# qsd67lc_v2.net
KiCad netlist of a schematic drawn in EAGLE
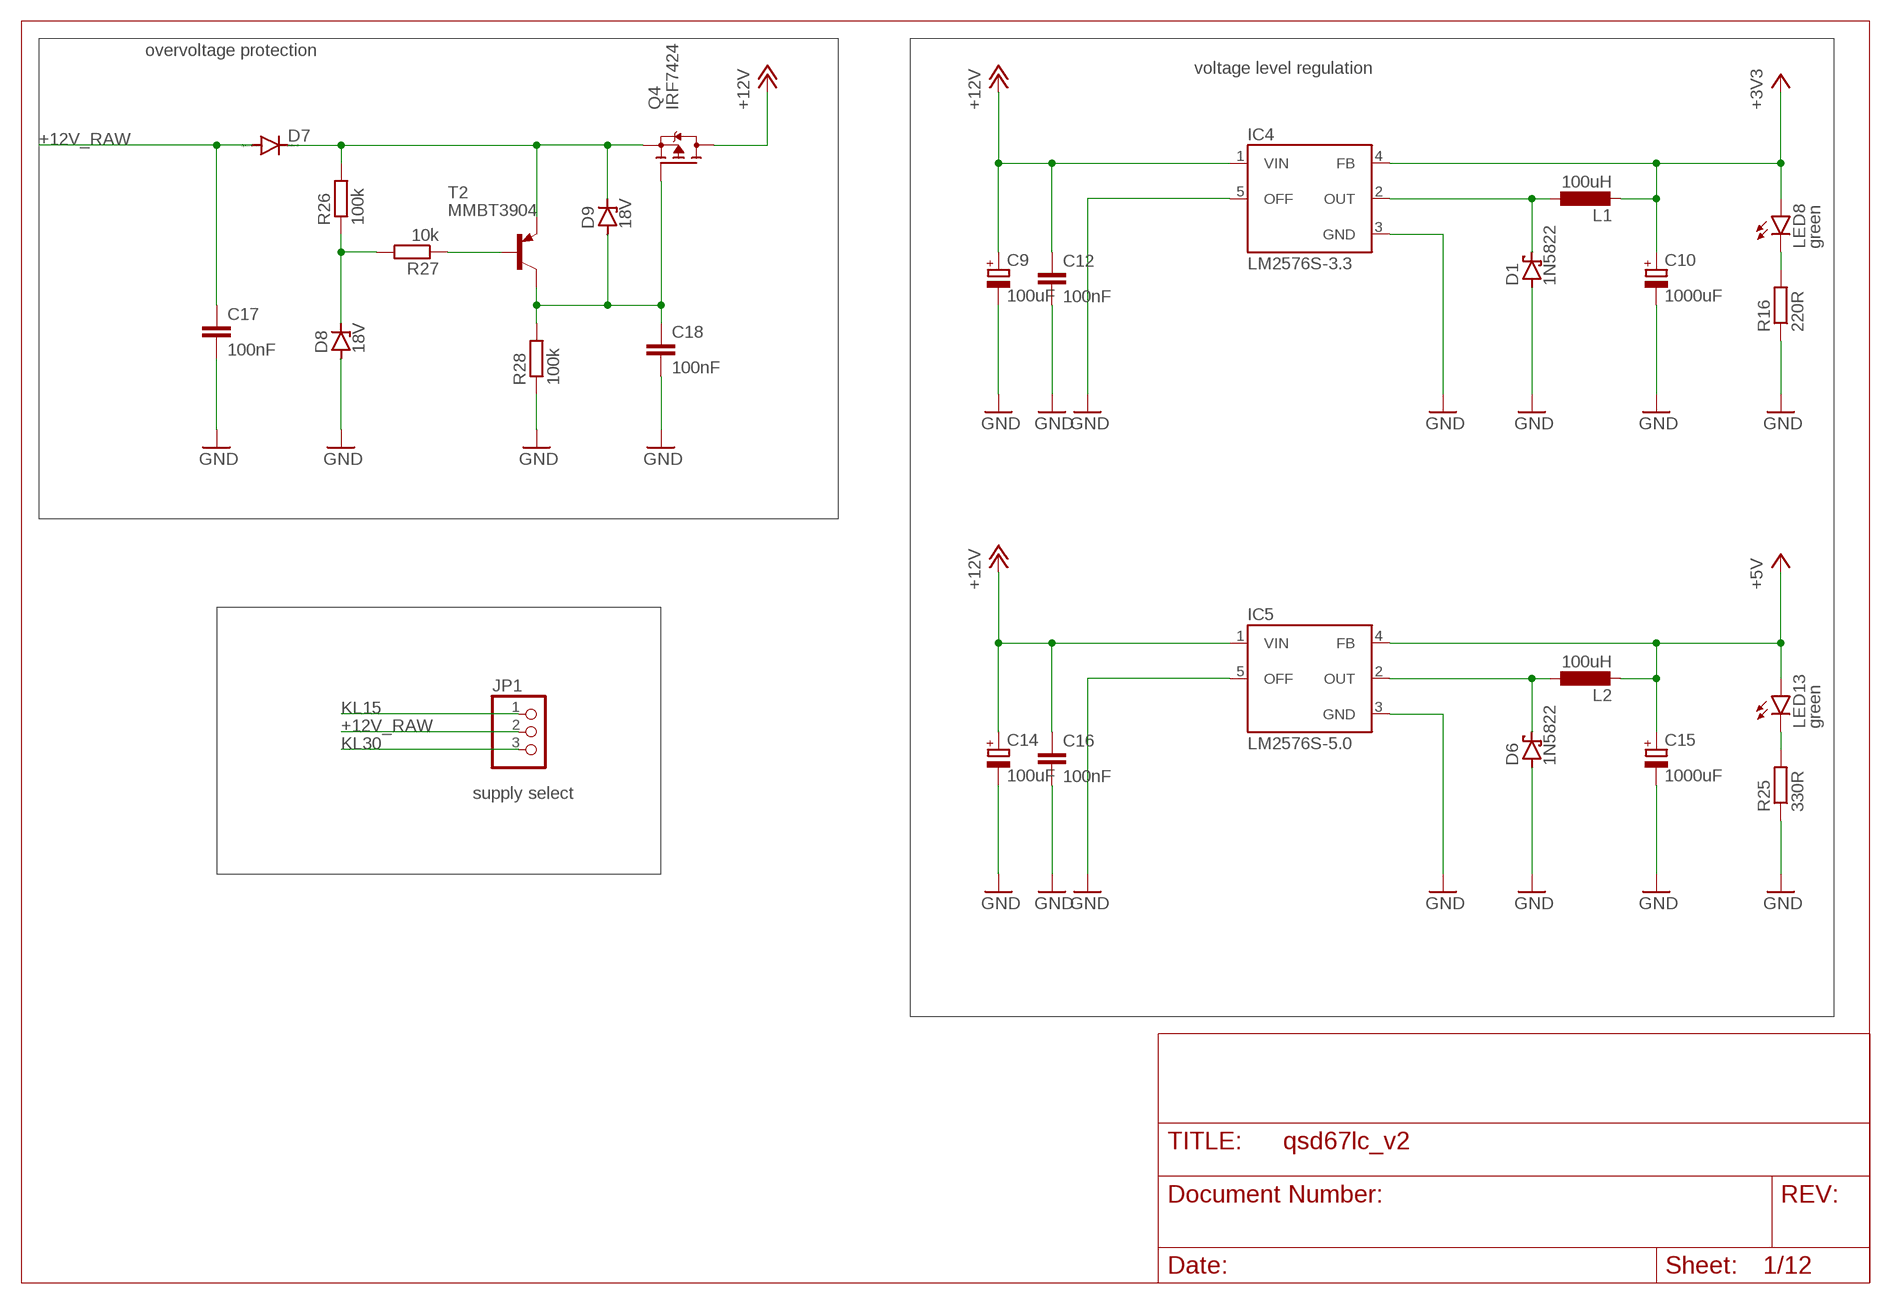
[diagram p0: schematic, sheet 1]
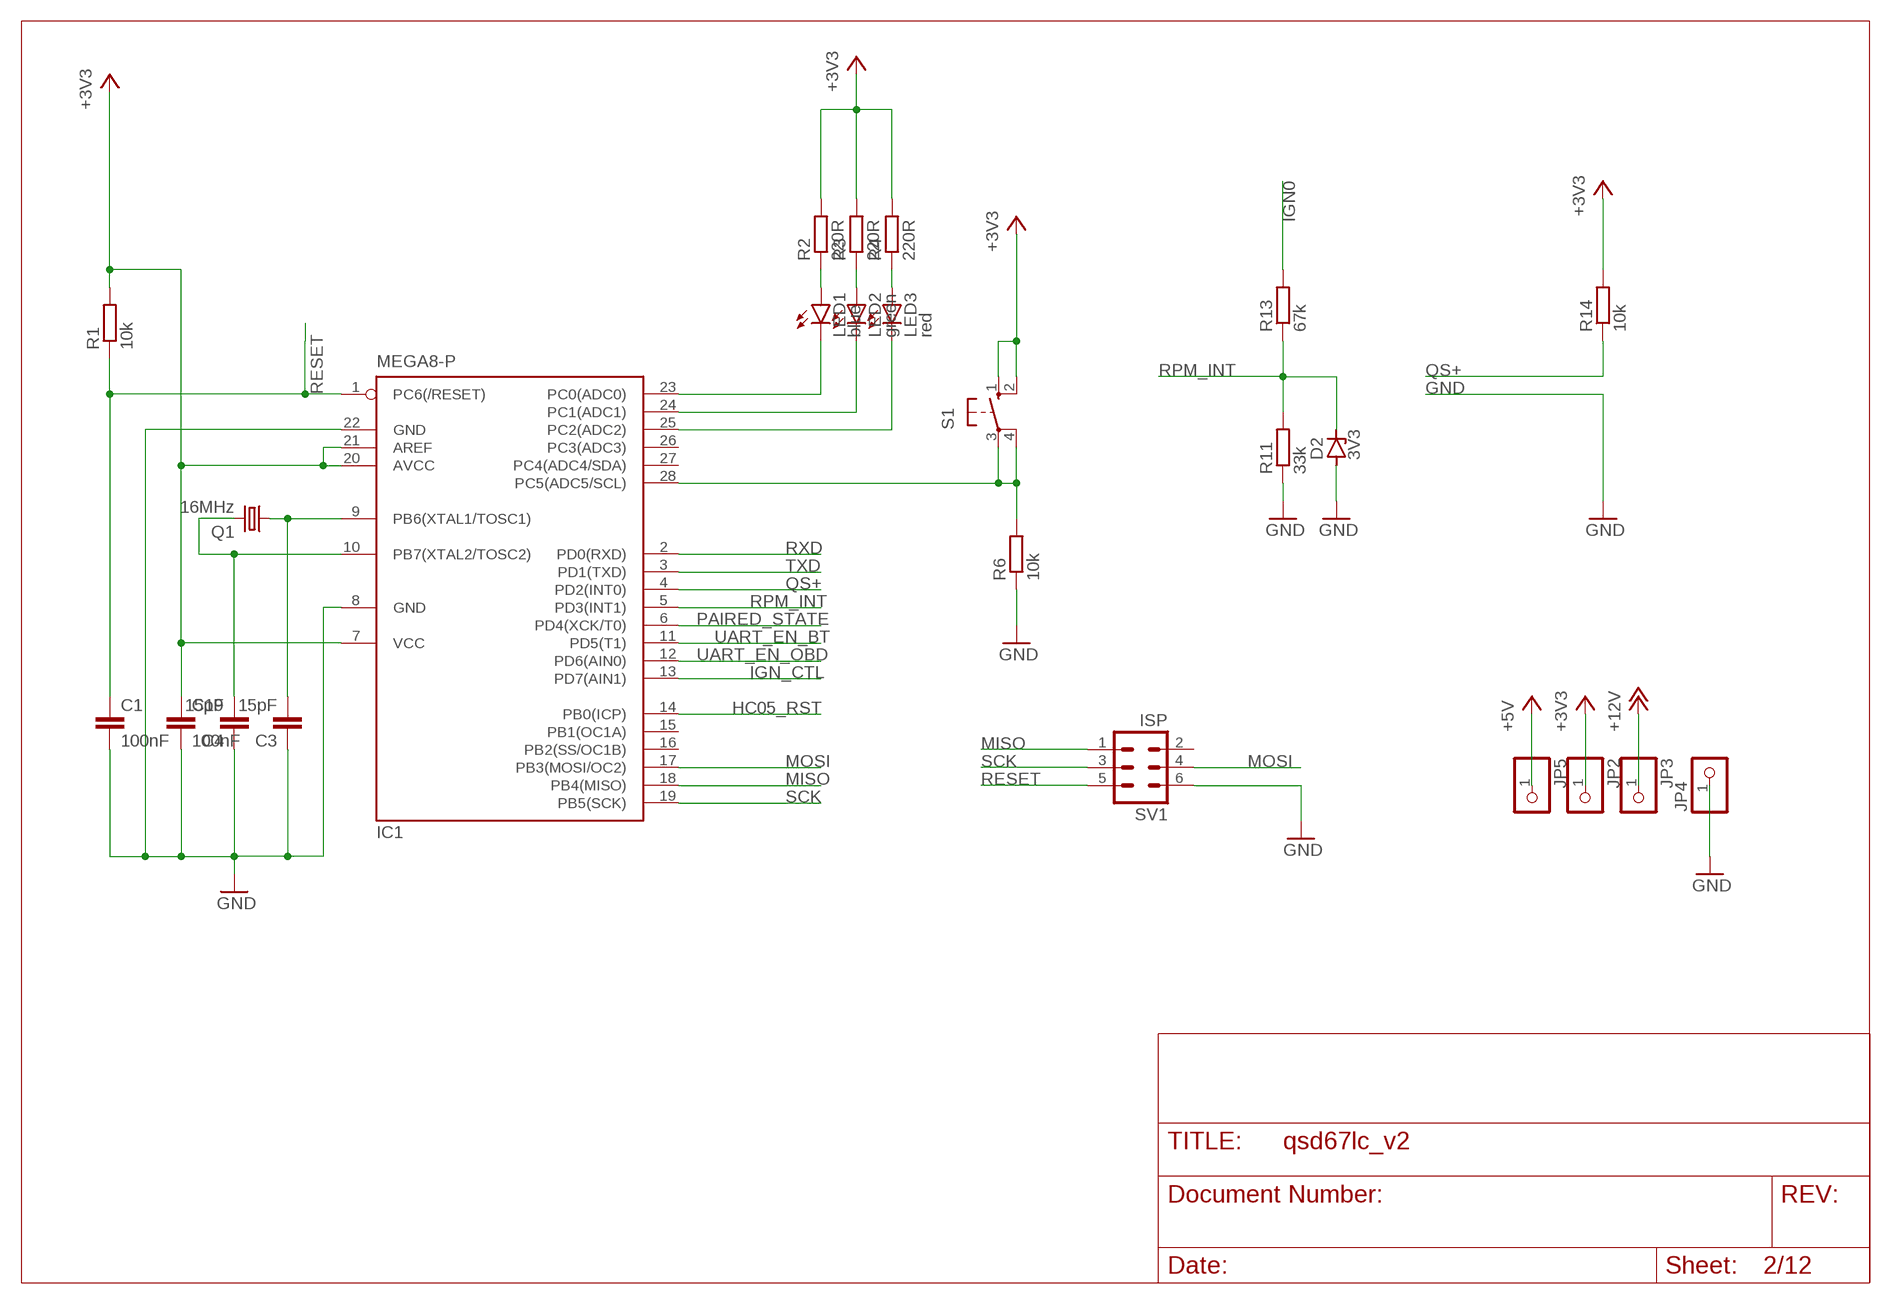
[diagram p1: schematic, sheet 2]
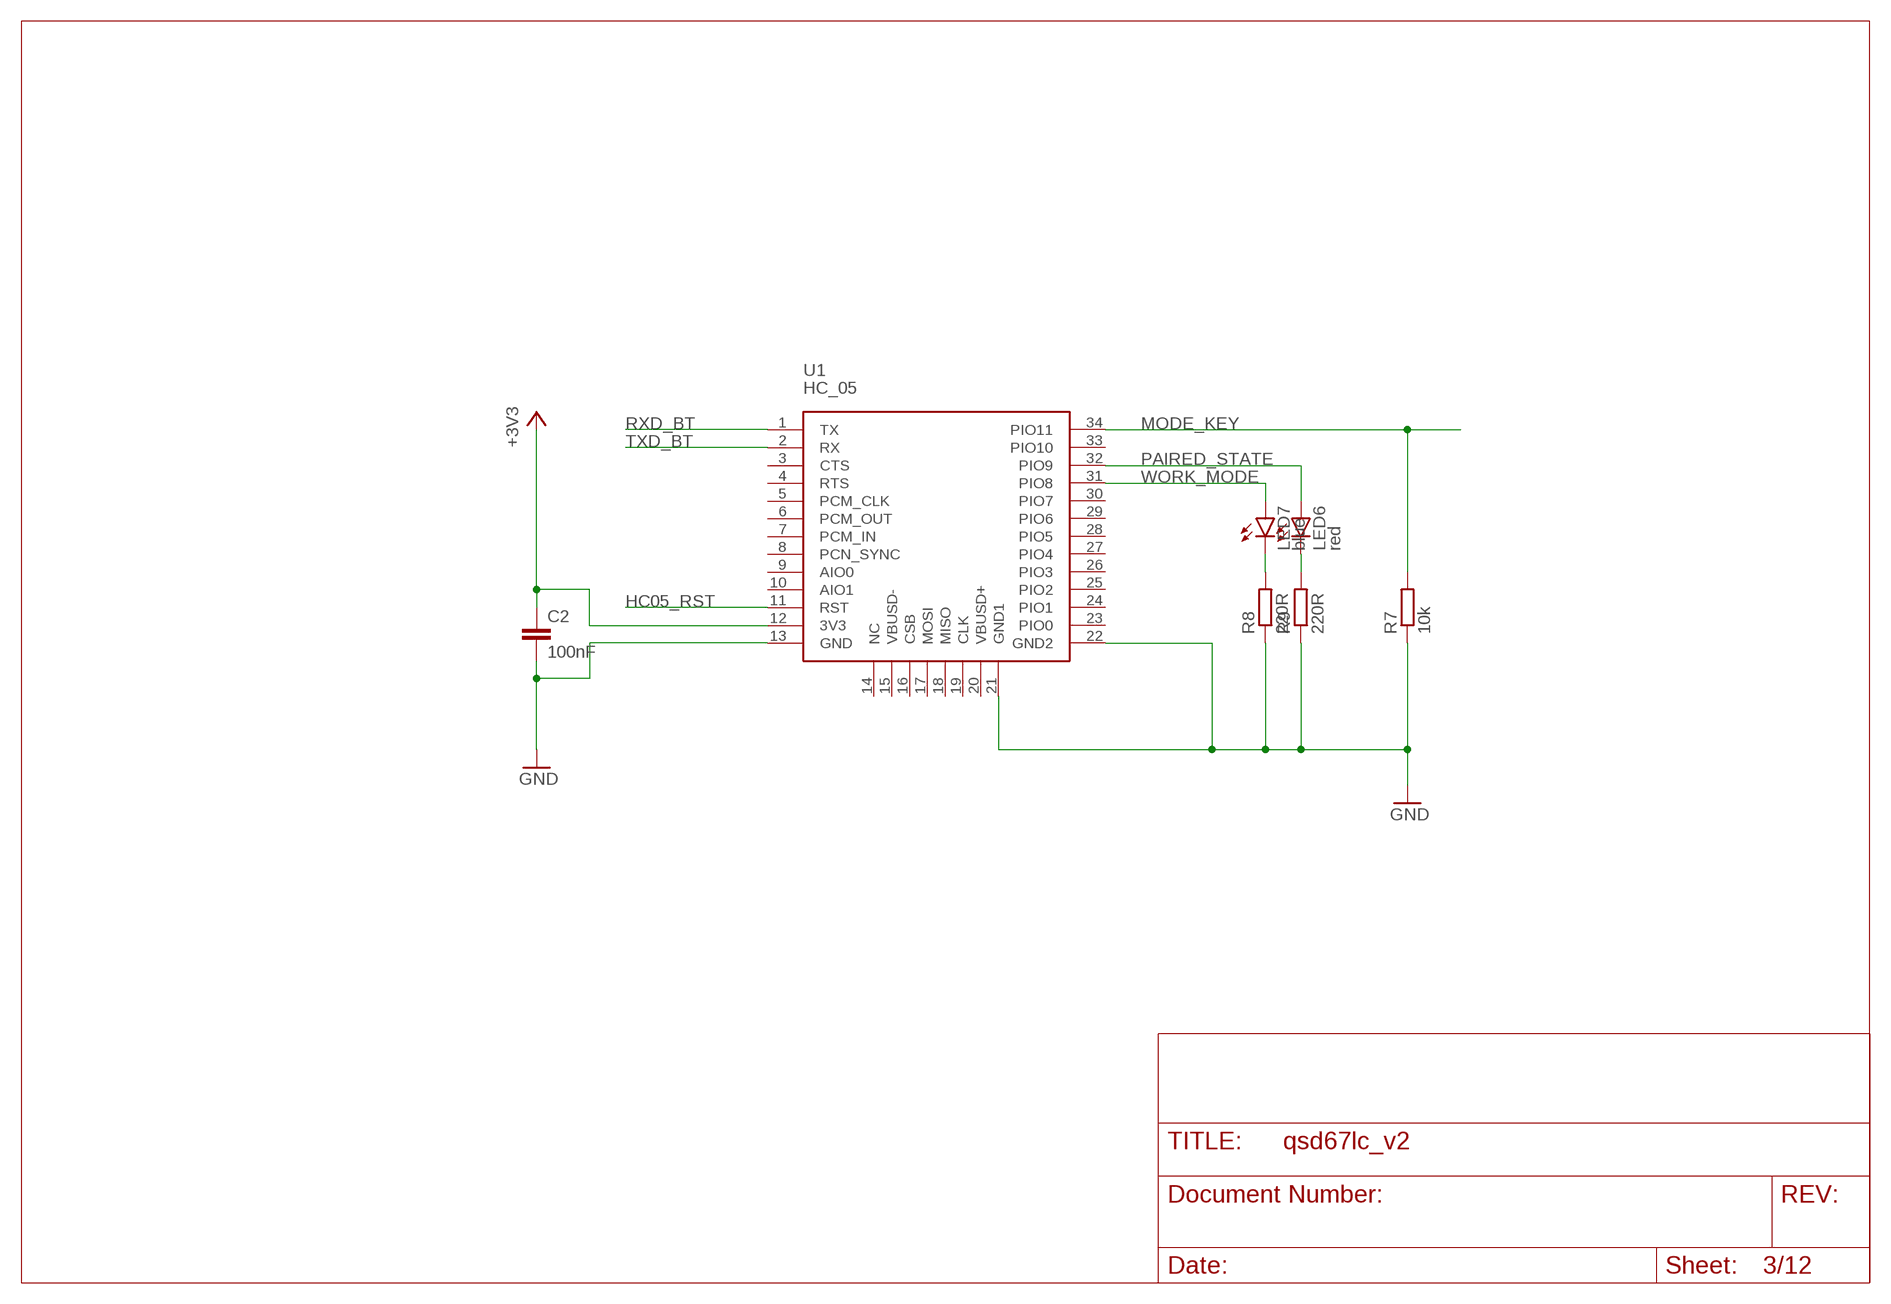
[diagram p2: schematic, sheet 3]
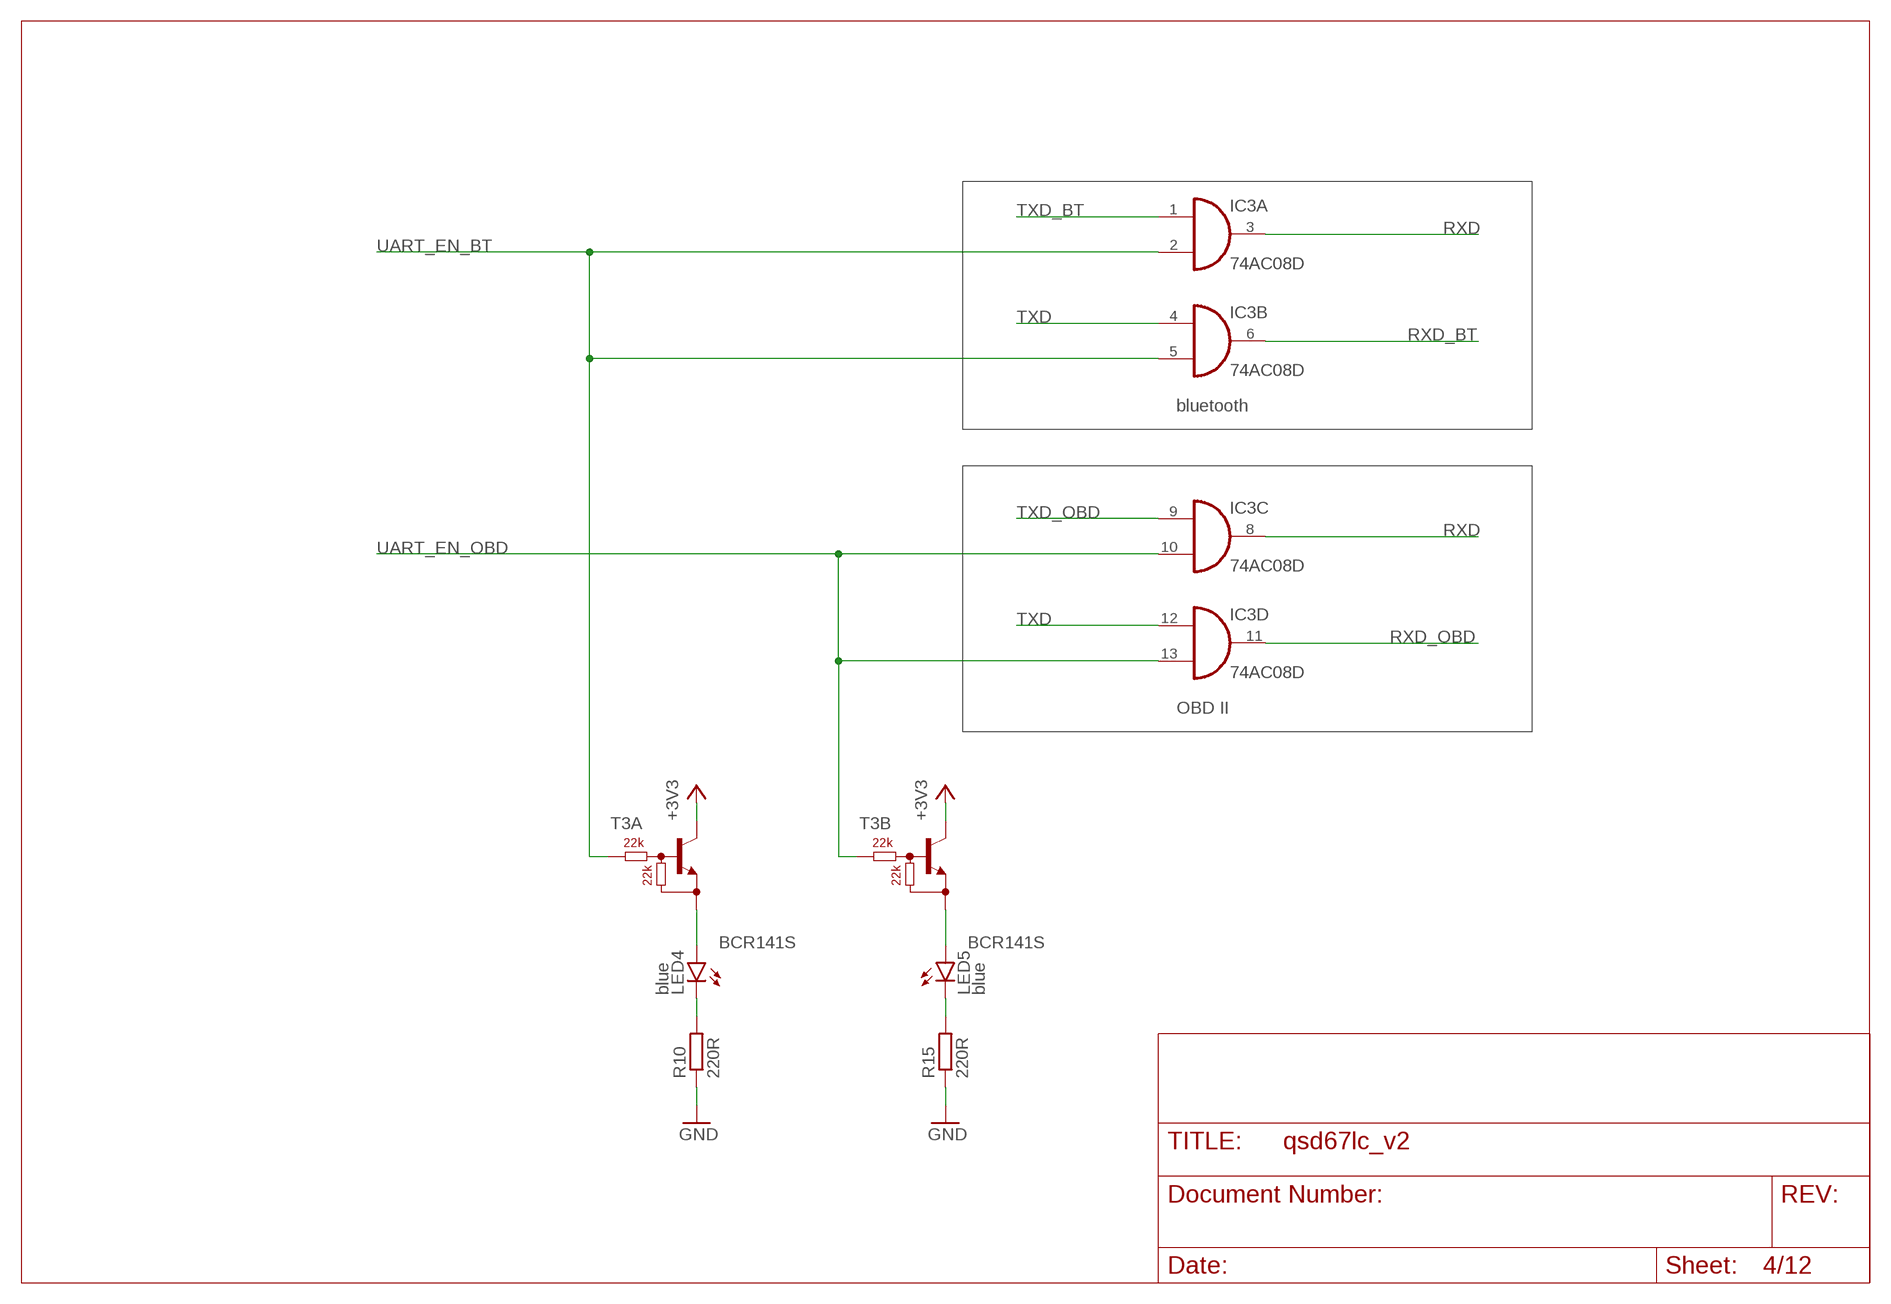
[diagram p3: schematic, sheet 4]
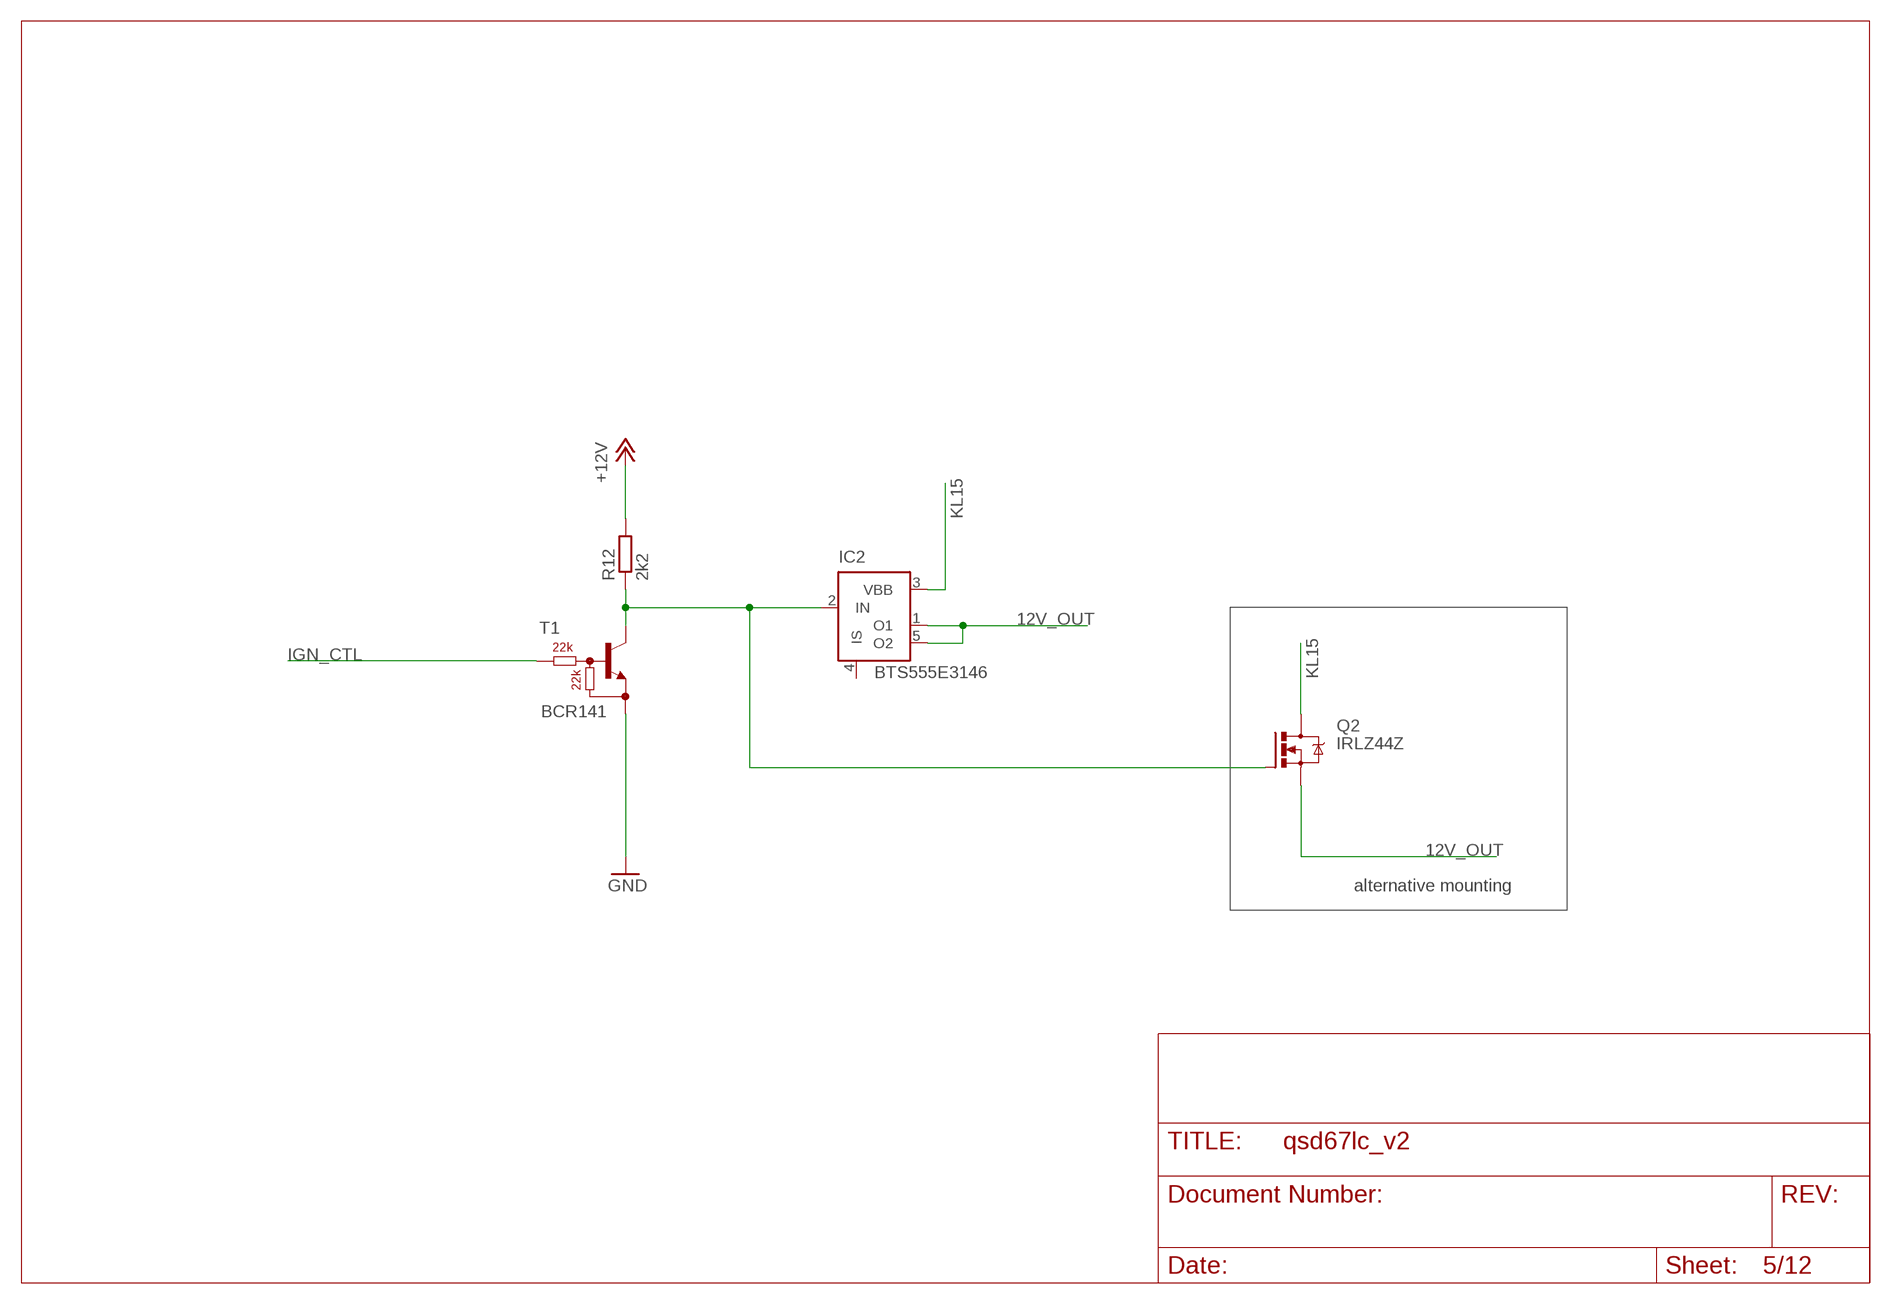
[diagram p4: schematic, sheet 5]
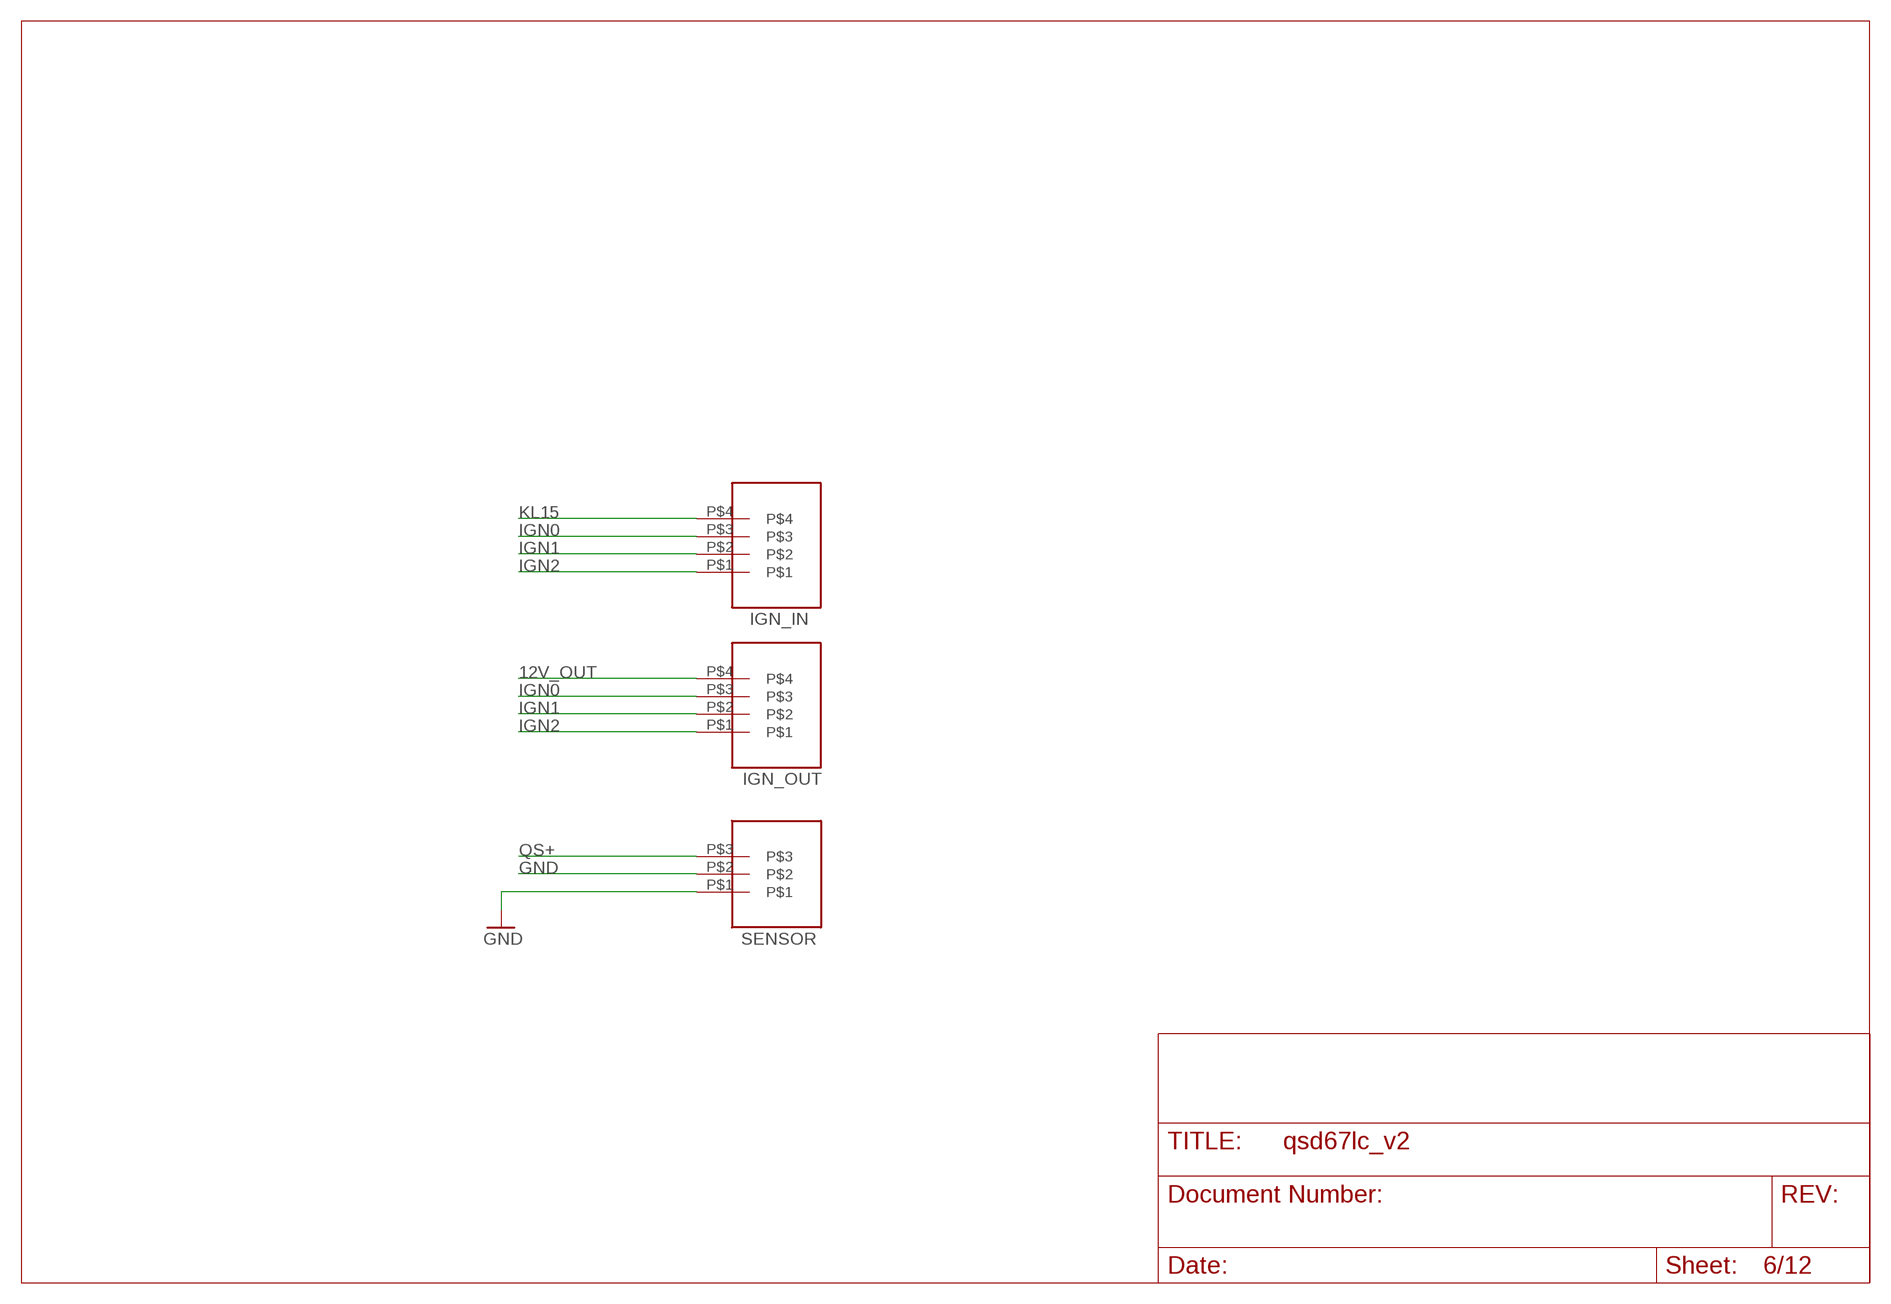
[diagram p5: schematic, sheet 6]
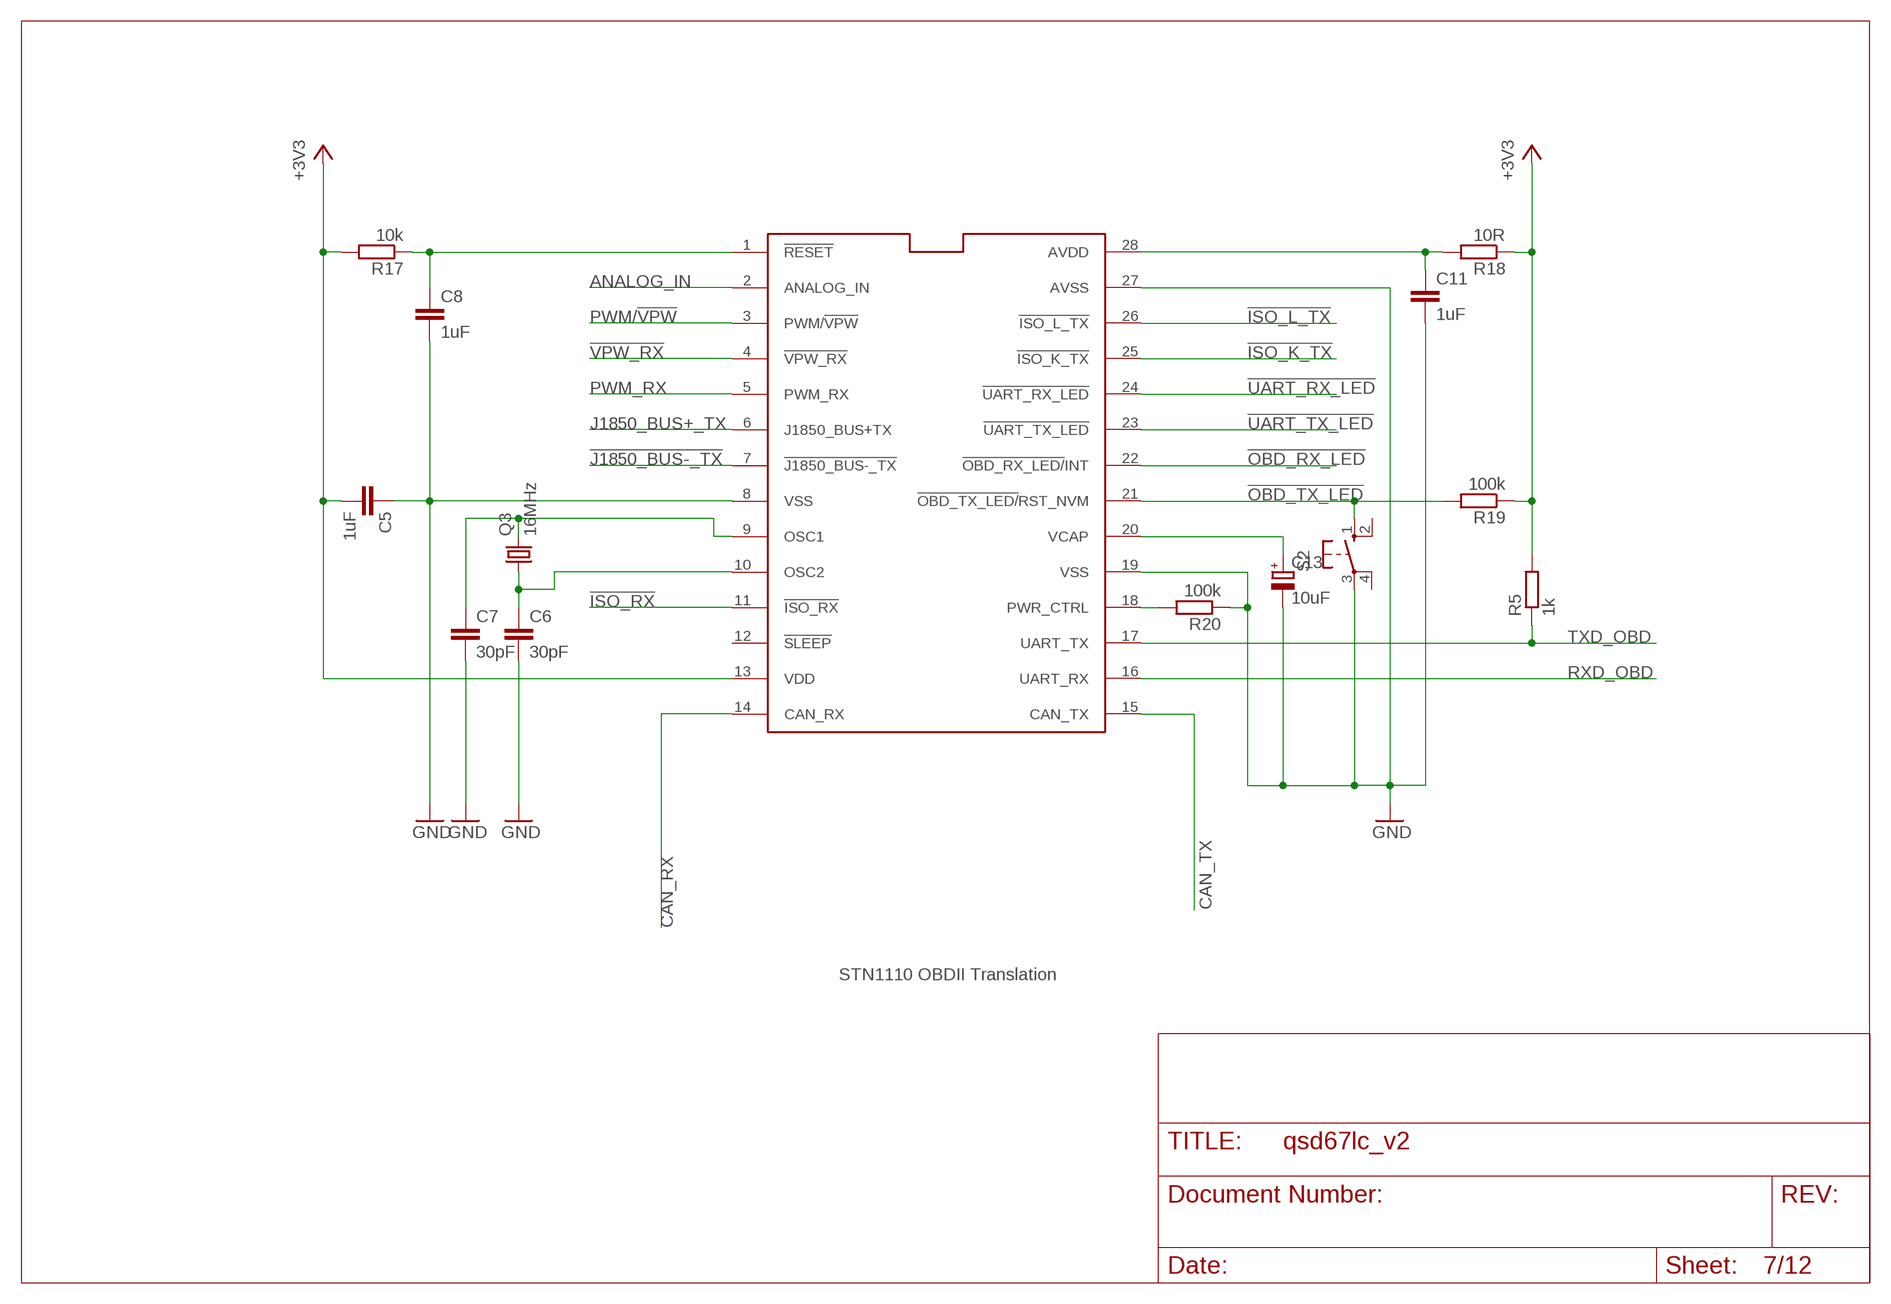
[diagram p6: schematic, sheet 7]
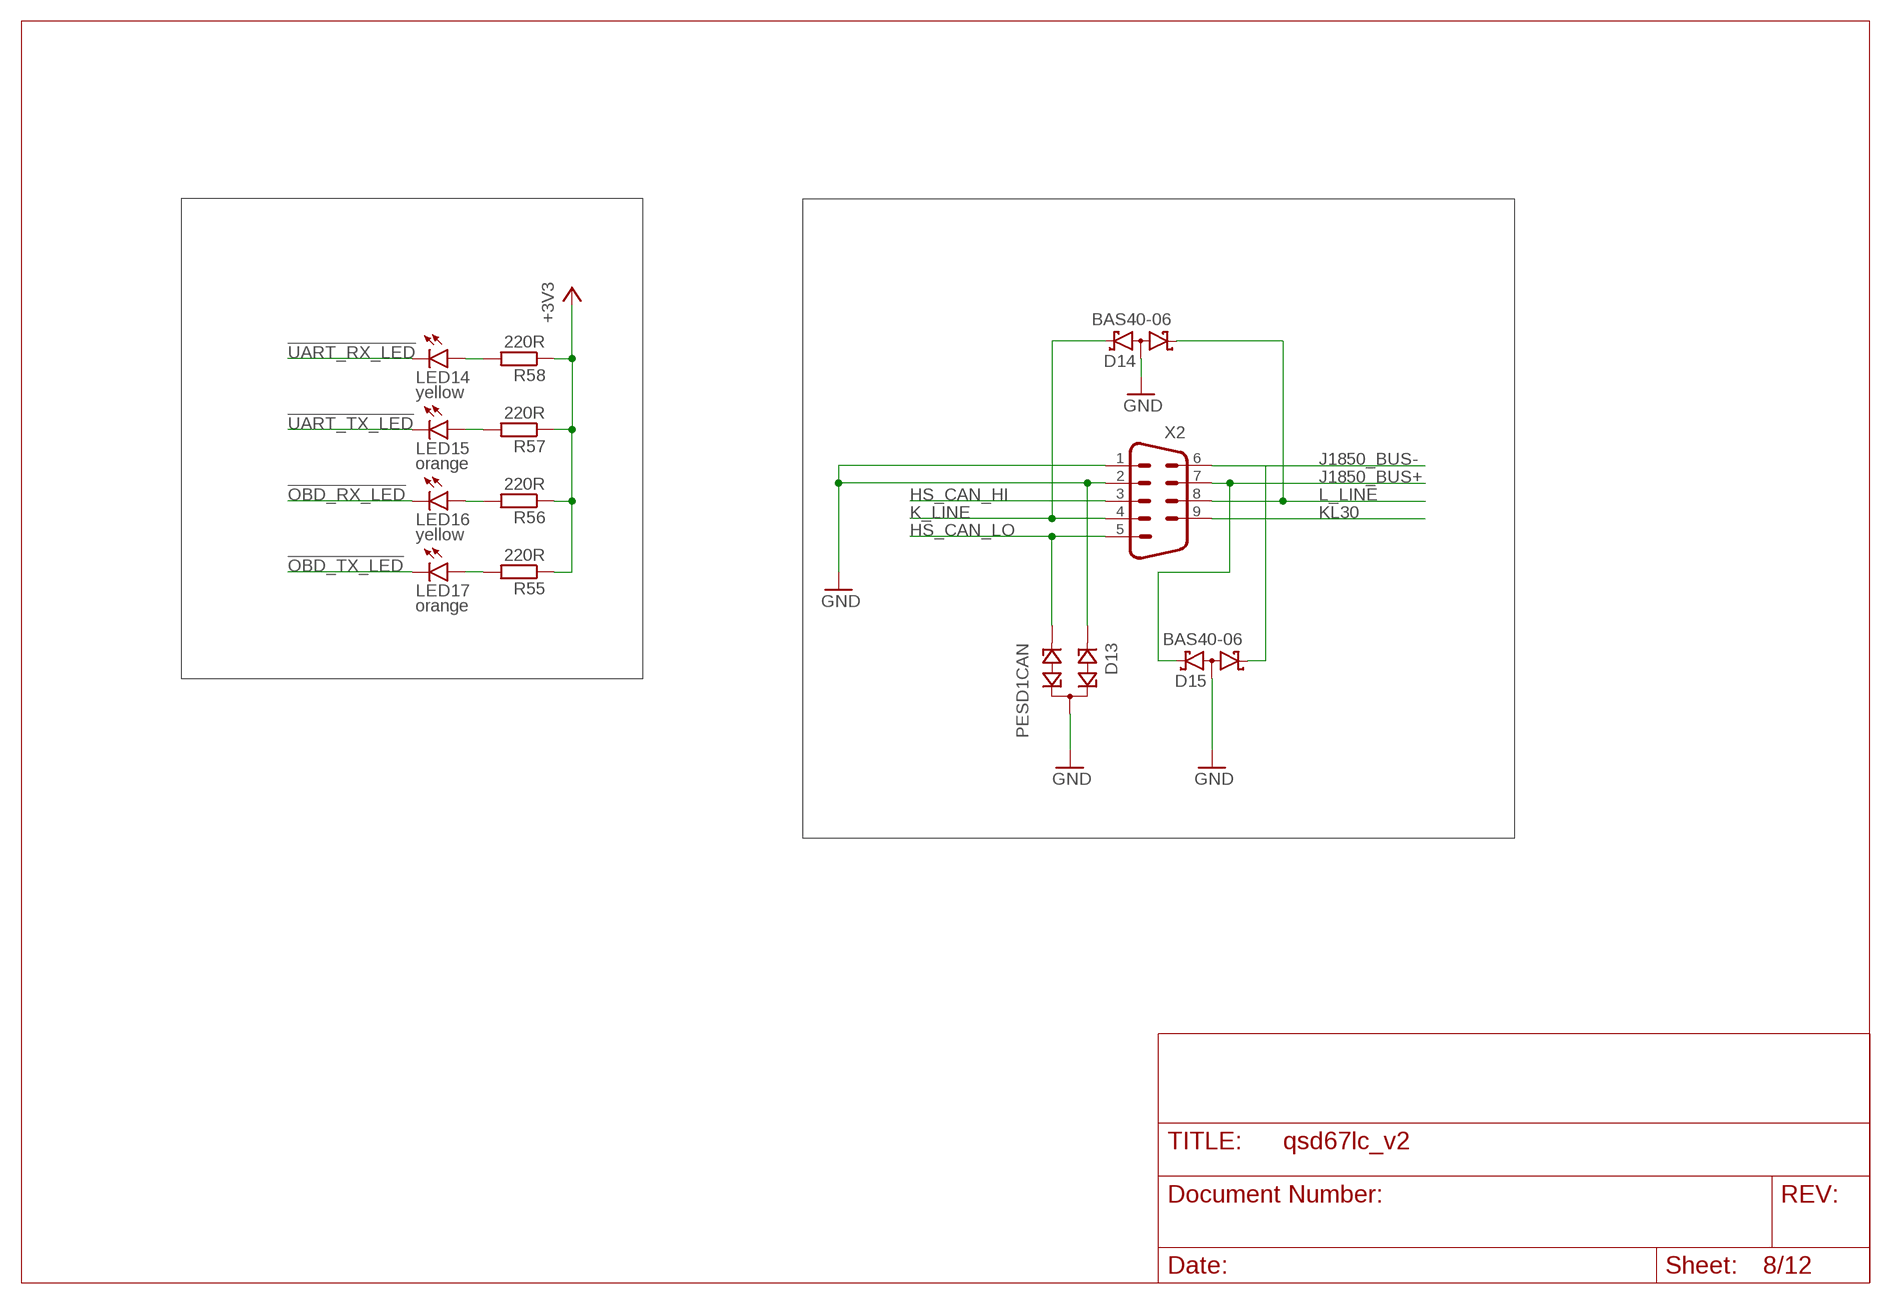
[diagram p7: schematic, sheet 8]
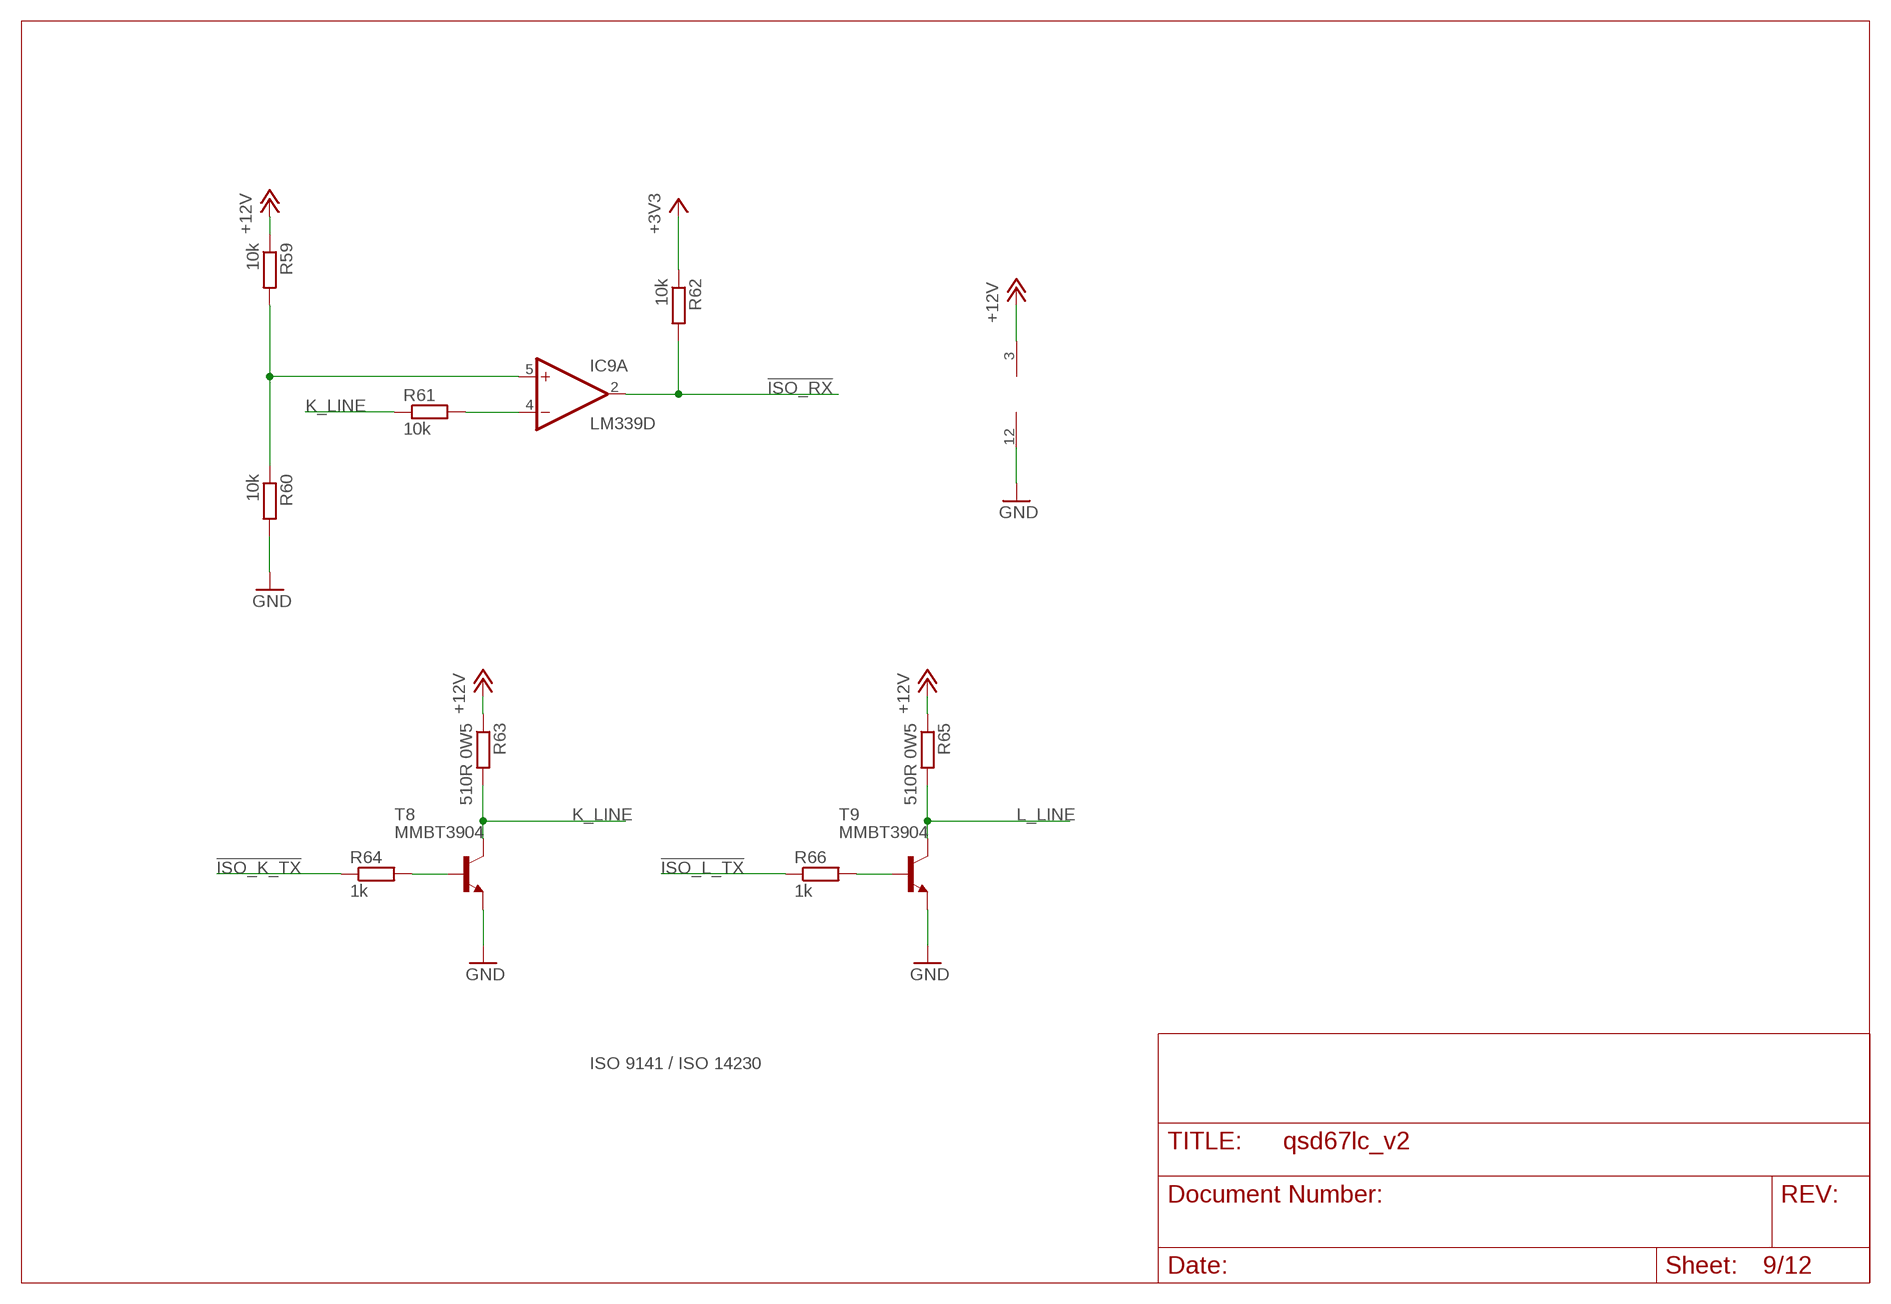
[diagram p8: schematic, sheet 9]
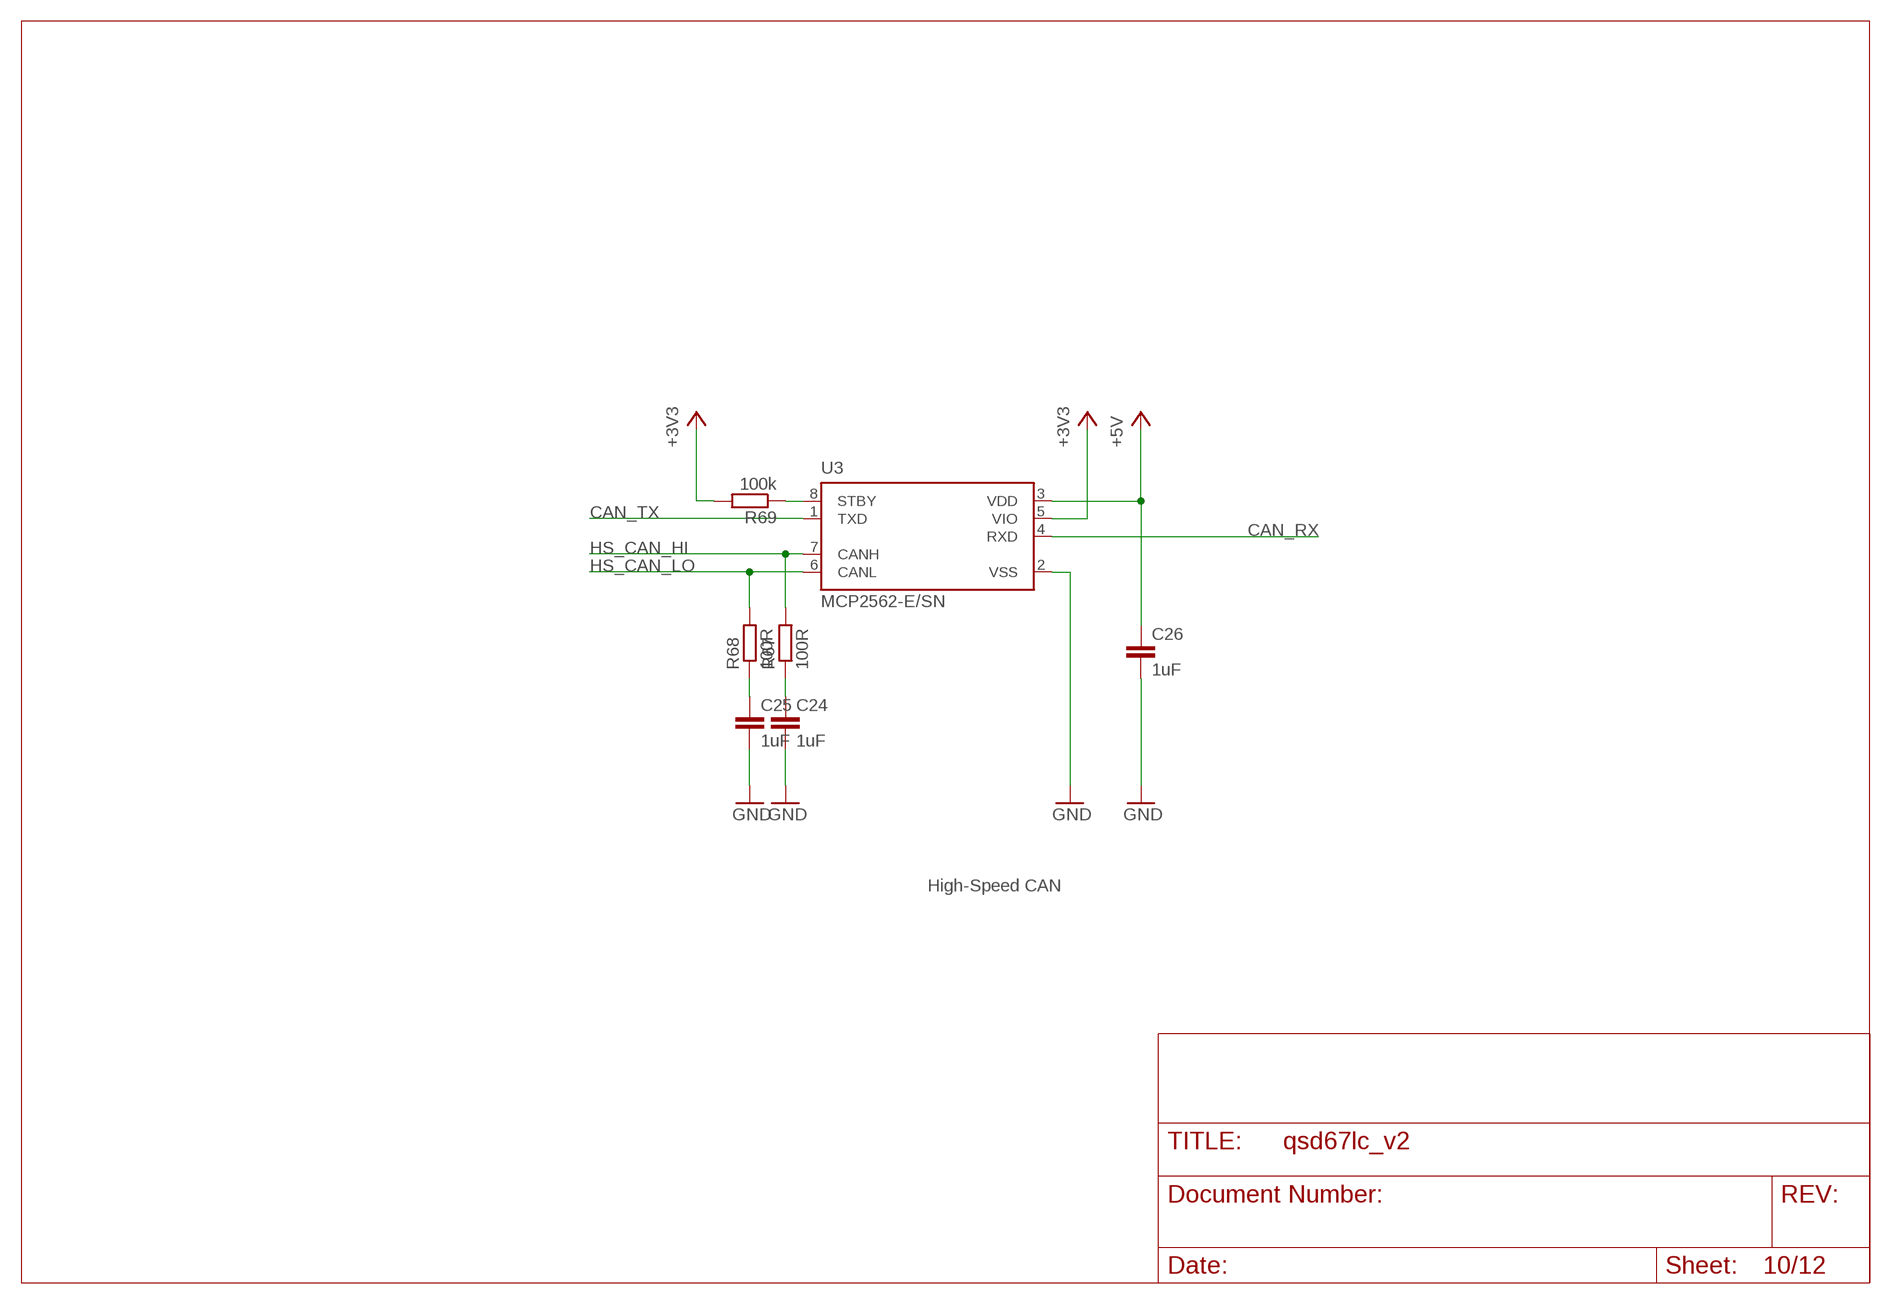
[diagram p9: schematic, sheet 10]
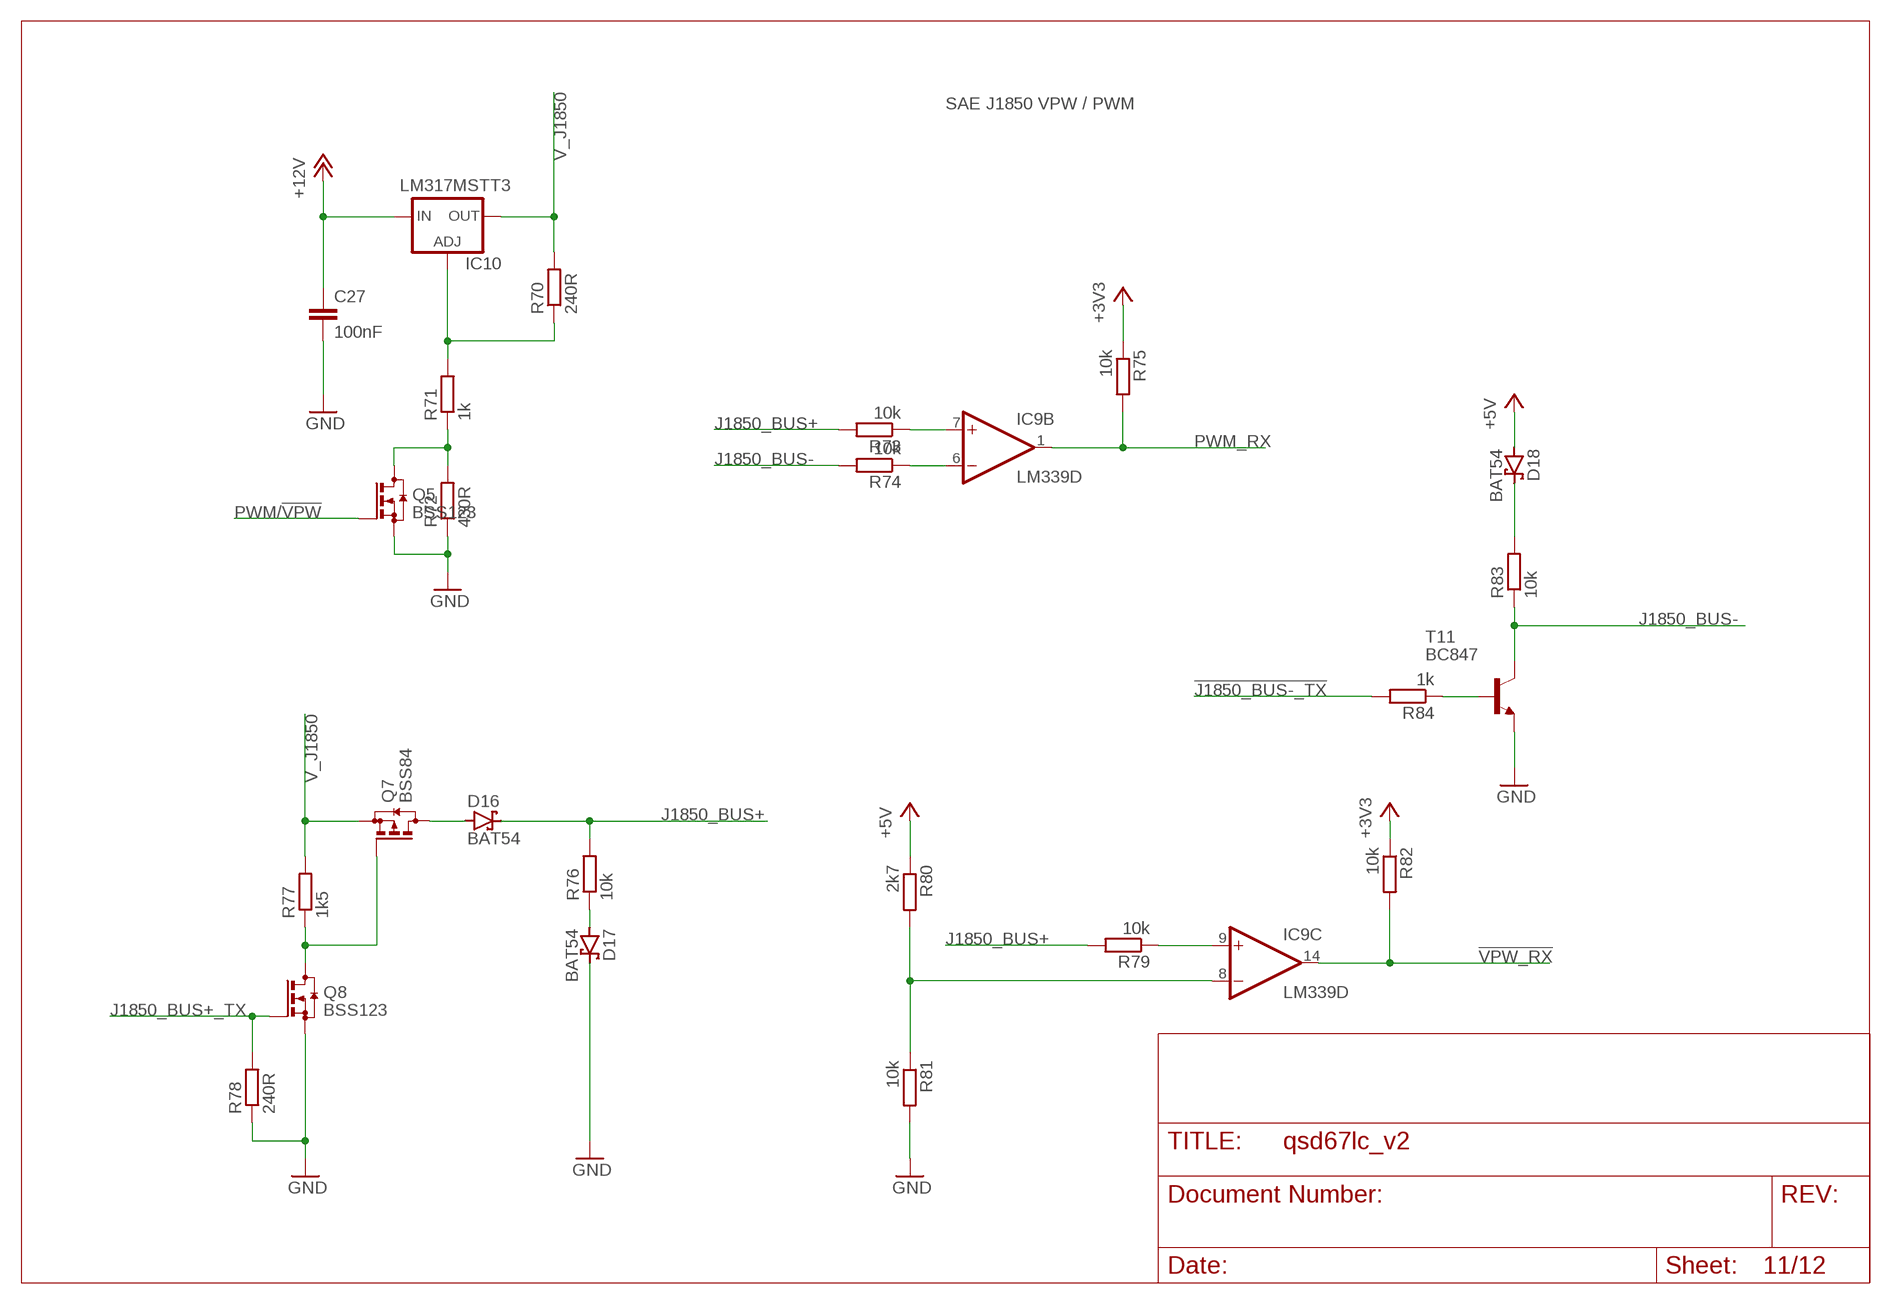
[diagram p10: schematic, sheet 11]
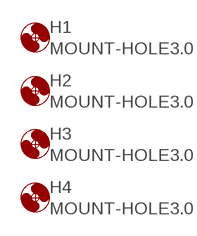
[diagram p11: schematic, sheet 12]

(export (version "E")
  (design (tool "Eeschema 10.0.6"))
  (components
    (comp (ref "C27")
      (value "100nF")
      (footprint "eagle-import:C0805")
      (libsource (lib "eagle-import") (part "C-EUC0805"))
    )
    (comp (ref "D16")
      (value "BAT54")
      (footprint "eagle-import:SOT23")
      (libsource (lib "eagle-import") (part "BAT54"))
    )
    (comp (ref "D17")
      (value "BAT54")
      (footprint "eagle-import:SOT23")
      (libsource (lib "eagle-import") (part "BAT54"))
    )
    (comp (ref "D18")
      (value "BAT54")
      (footprint "eagle-import:SOT23")
      (libsource (lib "eagle-import") (part "BAT54"))
    )
    (comp (ref "IC9")
      (value "LM339D")
      (footprint "eagle-import:SO14")
      (libsource (lib "eagle-import") (part "LM339D"))
    )
    (comp (ref "IC10")
      (value "LM317MSTT3")
      (footprint "eagle-import:SOT223")
      (libsource (lib "eagle-import") (part "LM317?MSTT3"))
    )
    (comp (ref "Q5")
      (value "BSS123")
      (footprint "eagle-import:SOT23")
      (libsource (lib "eagle-import") (part "BSS123"))
    )
    (comp (ref "Q7")
      (value "BSS84")
      (footprint "eagle-import:SOT23")
      (libsource (lib "eagle-import") (part "BSS84"))
    )
    (comp (ref "Q8")
      (value "BSS123")
      (footprint "eagle-import:SOT23")
      (libsource (lib "eagle-import") (part "BSS123"))
    )
    (comp (ref "R70")
      (value "240R")
      (footprint "eagle-import:R0805")
      (libsource (lib "eagle-import") (part "R-EU_R0805"))
    )
    (comp (ref "R71")
      (value "1k")
      (footprint "eagle-import:R0805")
      (libsource (lib "eagle-import") (part "R-EU_R0805"))
    )
    (comp (ref "R72")
      (value "430R")
      (footprint "eagle-import:R0805")
      (libsource (lib "eagle-import") (part "R-EU_R0805"))
    )
    (comp (ref "R73")
      (value "10k")
      (footprint "eagle-import:R0805")
      (libsource (lib "eagle-import") (part "R-EU_R0805"))
    )
    (comp (ref "R74")
      (value "10k")
      (footprint "eagle-import:R0805")
      (libsource (lib "eagle-import") (part "R-EU_R0805"))
    )
    (comp (ref "R75")
      (value "10k")
      (footprint "eagle-import:R0805")
      (libsource (lib "eagle-import") (part "R-EU_R0805"))
    )
    (comp (ref "R76")
      (value "10k")
      (footprint "eagle-import:R0805")
      (libsource (lib "eagle-import") (part "R-EU_R0805"))
    )
    (comp (ref "R77")
      (value "1k5")
      (footprint "eagle-import:R0805")
      (libsource (lib "eagle-import") (part "R-EU_R0805"))
    )
    (comp (ref "R78")
      (value "240R")
      (footprint "eagle-import:R0805")
      (libsource (lib "eagle-import") (part "R-EU_R0805"))
    )
    (comp (ref "R79")
      (value "10k")
      (footprint "eagle-import:R0805")
      (libsource (lib "eagle-import") (part "R-EU_R0805"))
    )
    (comp (ref "R80")
      (value "2k7")
      (footprint "eagle-import:R0805")
      (libsource (lib "eagle-import") (part "R-EU_R0805"))
    )
    (comp (ref "R81")
      (value "10k")
      (footprint "eagle-import:R0805")
      (libsource (lib "eagle-import") (part "R-EU_R0805"))
    )
    (comp (ref "R82")
      (value "10k")
      (footprint "eagle-import:R0805")
      (libsource (lib "eagle-import") (part "R-EU_R0805"))
    )
    (comp (ref "R83")
      (value "10k")
      (footprint "eagle-import:R0805")
      (libsource (lib "eagle-import") (part "R-EU_R0805"))
    )
    (comp (ref "R84")
      (value "1k")
      (footprint "eagle-import:R0805")
      (libsource (lib "eagle-import") (part "R-EU_R0805"))
    )
    (comp (ref "T11")
      (value "BC847")
      (footprint "eagle-import:SOT23")
      (libsource (lib "eagle-import") (part "BC847"))
    )
    (comp (ref "C9")
      (value "100uF")
      (footprint "eagle-import:E5-10,5")
      (libsource (lib "eagle-import") (part "CPOL-EUE5-10.5"))
    )
    (comp (ref "C10")
      (value "1000uF")
      (footprint "eagle-import:E5-10,5")
      (libsource (lib "eagle-import") (part "CPOL-EUE5-10.5"))
    )
    (comp (ref "C12")
      (value "100nF")
      (footprint "eagle-import:C0805")
      (libsource (lib "eagle-import") (part "C-EUC0805"))
    )
    (comp (ref "C14")
      (value "100uF")
      (footprint "eagle-import:E5-10,5")
      (libsource (lib "eagle-import") (part "CPOL-EUE5-10.5"))
    )
    (comp (ref "C15")
      (value "1000uF")
      (footprint "eagle-import:E5-10,5")
      (libsource (lib "eagle-import") (part "CPOL-EUE5-10.5"))
    )
    (comp (ref "C16")
      (value "100nF")
      (footprint "eagle-import:C0805")
      (libsource (lib "eagle-import") (part "C-EUC0805"))
    )
    (comp (ref "C17")
      (value "100nF")
      (footprint "eagle-import:C0805")
      (libsource (lib "eagle-import") (part "C-EUC0805"))
    )
    (comp (ref "C18")
      (value "100nF")
      (footprint "eagle-import:C0805")
      (libsource (lib "eagle-import") (part "C-EUC0805"))
    )
    (comp (ref "D1")
      (value "1N5822")
      (footprint "eagle-import:DO201T15")
      (libsource (lib "eagle-import") (part "SCHOTTKY-DIODEDO201T15"))
    )
    (comp (ref "D6")
      (value "1N5822")
      (footprint "eagle-import:DO201T15")
      (libsource (lib "eagle-import") (part "SCHOTTKY-DIODEDO201T15"))
    )
    (comp (ref "D7")
      (value "DIODE-SOD123")
      (footprint "eagle-import:SOD123")
      (libsource (lib "eagle-import") (part "DIODE-SOD123"))
    )
    (comp (ref "D8")
      (value "18V")
      (footprint "eagle-import:SOD80C")
      (libsource (lib "eagle-import") (part "ZENER-DIODESOD80C"))
    )
    (comp (ref "D9")
      (value "18V")
      (footprint "eagle-import:SOD80C")
      (libsource (lib "eagle-import") (part "ZENER-DIODESOD80C"))
    )
    (comp (ref "IC4")
      (value "LM2576S-3.3")
      (footprint "eagle-import:TO263-5")
      (libsource (lib "eagle-import") (part "LM2576S"))
    )
    (comp (ref "IC5")
      (value "LM2576S-5.0")
      (footprint "eagle-import:TO263-5")
      (libsource (lib "eagle-import") (part "LM2576S"))
    )
    (comp (ref "JP1")
      (value "PINHD-1X3")
      (footprint "eagle-import:1X03")
      (libsource (lib "eagle-import") (part "PINHD-1X3"))
    )
    (comp (ref "L1")
      (value "100uH")
      (footprint "eagle-import:09HCP")
      (libsource (lib "eagle-import") (part "L-LEU-09HCP"))
    )
    (comp (ref "L2")
      (value "100uH")
      (footprint "eagle-import:09HCP")
      (libsource (lib "eagle-import") (part "L-LEU-09HCP"))
    )
    (comp (ref "LED8")
      (value "green")
      (footprint "eagle-import:CHIP-LED0805")
      (libsource (lib "eagle-import") (part "LEDCHIP-LED0805"))
    )
    (comp (ref "LED13")
      (value "green")
      (footprint "eagle-import:CHIP-LED0805")
      (libsource (lib "eagle-import") (part "LEDCHIP-LED0805"))
    )
    (comp (ref "Q4")
      (value "IRF7424")
      (footprint "eagle-import:SO-8")
      (libsource (lib "eagle-import") (part "BSO201SP"))
    )
    (comp (ref "R16")
      (value "220R")
      (footprint "eagle-import:R0805")
      (libsource (lib "eagle-import") (part "R-EU_R0805"))
    )
    (comp (ref "R25")
      (value "330R")
      (footprint "eagle-import:R0805")
      (libsource (lib "eagle-import") (part "R-EU_R0805"))
    )
    (comp (ref "R26")
      (value "100k")
      (footprint "eagle-import:R0805")
      (libsource (lib "eagle-import") (part "R-EU_R0805"))
    )
    (comp (ref "R27")
      (value "10k")
      (footprint "eagle-import:R0805")
      (libsource (lib "eagle-import") (part "R-EU_R0805"))
    )
    (comp (ref "R28")
      (value "100k")
      (footprint "eagle-import:R0805")
      (libsource (lib "eagle-import") (part "R-EU_R0805"))
    )
    (comp (ref "T2")
      (value "MMBT3904")
      (footprint "eagle-import:SOT23-BEC")
      (libsource (lib "eagle-import") (part "-PNP-SOT23-BECBC807-16"))
    )
    (comp (ref "IC3")
      (value "74AC08D")
      (footprint "eagle-import:SO14")
      (libsource (lib "eagle-import") (part "7408DAC"))
    )
    (comp (ref "LED4")
      (value "blue")
      (footprint "eagle-import:CHIP-LED0805")
      (libsource (lib "eagle-import") (part "LEDCHIP-LED0805"))
    )
    (comp (ref "LED5")
      (value "blue")
      (footprint "eagle-import:CHIP-LED0805")
      (libsource (lib "eagle-import") (part "LEDCHIP-LED0805"))
    )
    (comp (ref "R10")
      (value "220R")
      (footprint "eagle-import:M0805")
      (libsource (lib "eagle-import") (part "R-EU_M0805"))
    )
    (comp (ref "R15")
      (value "220R")
      (footprint "eagle-import:M0805")
      (libsource (lib "eagle-import") (part "R-EU_M0805"))
    )
    (comp (ref "T3")
      (value "BCR141S")
      (footprint "eagle-import:SOT363_INFINEON")
      (libsource (lib "eagle-import") (part "BCR141S"))
    )
    (comp (ref "H1")
      (value "MOUNT-HOLE3.0")
      (footprint "eagle-import:3,0")
      (libsource (lib "eagle-import") (part "MOUNT-HOLE3.0"))
    )
    (comp (ref "H2")
      (value "MOUNT-HOLE3.0")
      (footprint "eagle-import:3,0")
      (libsource (lib "eagle-import") (part "MOUNT-HOLE3.0"))
    )
    (comp (ref "H3")
      (value "MOUNT-HOLE3.0")
      (footprint "eagle-import:3,0")
      (libsource (lib "eagle-import") (part "MOUNT-HOLE3.0"))
    )
    (comp (ref "H4")
      (value "MOUNT-HOLE3.0")
      (footprint "eagle-import:3,0")
      (libsource (lib "eagle-import") (part "MOUNT-HOLE3.0"))
    )
    (comp (ref "C24")
      (value "1uF")
      (footprint "eagle-import:C0805")
      (libsource (lib "eagle-import") (part "C-EUC0805"))
    )
    (comp (ref "C25")
      (value "1uF")
      (footprint "eagle-import:C0805")
      (libsource (lib "eagle-import") (part "C-EUC0805"))
    )
    (comp (ref "C26")
      (value "1uF")
      (footprint "eagle-import:C0805")
      (libsource (lib "eagle-import") (part "C-EUC0805"))
    )
    (comp (ref "R67")
      (value "100R")
      (footprint "eagle-import:R0805")
      (libsource (lib "eagle-import") (part "R-EU_R0805"))
    )
    (comp (ref "R68")
      (value "100R")
      (footprint "eagle-import:R0805")
      (libsource (lib "eagle-import") (part "R-EU_R0805"))
    )
    (comp (ref "R69")
      (value "100k")
      (footprint "eagle-import:R0805")
      (libsource (lib "eagle-import") (part "R-EU_R0805"))
    )
    (comp (ref "U3")
      (value "MCP2562-E/SN")
      (footprint "eagle-import:SOIC127P600X175-8N")
      (fields (field (name "MF") "Microchip"))
      (libsource (lib "eagle-import") (part "MCP2562-E/SN"))
    )
    (comp (ref "C2")
      (value "100nF")
      (footprint "eagle-import:C0805")
      (libsource (lib "eagle-import") (part "C-EUC0805"))
    )
    (comp (ref "LED6")
      (value "red")
      (footprint "eagle-import:CHIP-LED0805")
      (libsource (lib "eagle-import") (part "LEDCHIP-LED0805"))
    )
    (comp (ref "LED7")
      (value "blue")
      (footprint "eagle-import:CHIP-LED0805")
      (libsource (lib "eagle-import") (part "LEDCHIP-LED0805"))
    )
    (comp (ref "R7")
      (value "10k")
      (footprint "eagle-import:R0805")
      (libsource (lib "eagle-import") (part "R-EU_R0805"))
    )
    (comp (ref "R8")
      (value "220R")
      (footprint "eagle-import:R0805")
      (libsource (lib "eagle-import") (part "R-EU_R0805"))
    )
    (comp (ref "R9")
      (value "220R")
      (footprint "eagle-import:R0805")
      (libsource (lib "eagle-import") (part "R-EU_R0805"))
    )
    (comp (ref "U1")
      (value "HC_05")
      (footprint "eagle-import:BLUETOOTH_SMD")
      (libsource (lib "eagle-import") (part "HC_05"))
    )
    (comp (ref "C1")
      (value "100nF")
      (footprint "eagle-import:C0805")
      (libsource (lib "eagle-import") (part "C-EUC0805"))
    )
    (comp (ref "C3")
      (value "15pF")
      (footprint "eagle-import:C0805")
      (libsource (lib "eagle-import") (part "C-EUC0805"))
    )
    (comp (ref "C4")
      (value "15pF")
      (footprint "eagle-import:C0805")
      (libsource (lib "eagle-import") (part "C-EUC0805"))
    )
    (comp (ref "C19")
      (value "100nF")
      (footprint "eagle-import:C0805")
      (libsource (lib "eagle-import") (part "C-EUC0805"))
    )
    (comp (ref "D2")
      (value "3V3")
      (footprint "eagle-import:SOD80C")
      (libsource (lib "eagle-import") (part "ZENER-DIODESOD80C"))
    )
    (comp (ref "IC1")
      (value "MEGA8-P")
      (footprint "eagle-import:DIL28-3")
      (libsource (lib "eagle-import") (part "MEGA8-P"))
    )
    (comp (ref "JP2")
      (value "PINHD-1X1")
      (footprint "eagle-import:1X01")
      (libsource (lib "eagle-import") (part "PINHD-1X1"))
    )
    (comp (ref "JP3")
      (value "PINHD-1X1")
      (footprint "eagle-import:1X01")
      (libsource (lib "eagle-import") (part "PINHD-1X1"))
    )
    (comp (ref "JP4")
      (value "PINHD-1X1")
      (footprint "eagle-import:1X01")
      (libsource (lib "eagle-import") (part "PINHD-1X1"))
    )
    (comp (ref "JP5")
      (value "PINHD-1X1")
      (footprint "eagle-import:1X01")
      (libsource (lib "eagle-import") (part "PINHD-1X1"))
    )
    (comp (ref "LED1")
      (value "blue")
      (footprint "eagle-import:CHIP-LED0805")
      (libsource (lib "eagle-import") (part "LEDCHIP-LED0805"))
    )
    (comp (ref "LED2")
      (value "green")
      (footprint "eagle-import:CHIP-LED0805")
      (libsource (lib "eagle-import") (part "LEDCHIP-LED0805"))
    )
    (comp (ref "LED3")
      (value "red")
      (footprint "eagle-import:CHIP-LED0805")
      (libsource (lib "eagle-import") (part "LEDCHIP-LED0805"))
    )
    (comp (ref "Q1")
      (value "16MHz")
      (footprint "eagle-import:HC49U-V")
      (libsource (lib "eagle-import") (part "CRYSTALHC49U-V"))
    )
    (comp (ref "R1")
      (value "10k")
      (footprint "eagle-import:R0805")
      (libsource (lib "eagle-import") (part "R-EU_R0805"))
    )
    (comp (ref "R2")
      (value "220R")
      (footprint "eagle-import:R0805")
      (libsource (lib "eagle-import") (part "R-EU_R0805"))
    )
    (comp (ref "R3")
      (value "220R")
      (footprint "eagle-import:R0805")
      (libsource (lib "eagle-import") (part "R-EU_R0805"))
    )
    (comp (ref "R4")
      (value "220R")
      (footprint "eagle-import:R0805")
      (libsource (lib "eagle-import") (part "R-EU_R0805"))
    )
    (comp (ref "R6")
      (value "10k")
      (footprint "eagle-import:R0805")
      (libsource (lib "eagle-import") (part "R-EU_R0805"))
    )
    (comp (ref "R11")
      (value "33k")
      (footprint "eagle-import:R0805")
      (libsource (lib "eagle-import") (part "R-EU_R0805"))
    )
    (comp (ref "R13")
      (value "67k")
      (footprint "eagle-import:R0805")
      (libsource (lib "eagle-import") (part "R-EU_R0805"))
    )
    (comp (ref "R14")
      (value "10k")
      (footprint "eagle-import:R0805")
      (libsource (lib "eagle-import") (part "R-EU_R0805"))
    )
    (comp (ref "S1")
      (value "10-XX")
      (footprint "eagle-import:B3F-10XX")
      (fields (field (name "MPN") "B3F-1000"))
      (libsource (lib "eagle-import") (part "10-XX"))
    )
    (comp (ref "SV1")
      (value "ISP")
      (footprint "eagle-import:ML6")
      (libsource (lib "eagle-import") (part "ML6"))
    )
    (comp (ref "D13")
      (value "PESD1CAN")
      (footprint "eagle-import:SOT23")
      (libsource (lib "eagle-import") (part "PESD1CAN"))
    )
    (comp (ref "D14")
      (value "BAS40-06")
      (footprint "eagle-import:SOT23")
      (libsource (lib "eagle-import") (part "BAS40-06"))
    )
    (comp (ref "D15")
      (value "BAS40-06")
      (footprint "eagle-import:SOT23")
      (libsource (lib "eagle-import") (part "BAS40-06"))
    )
    (comp (ref "LED14")
      (value "yellow")
      (footprint "eagle-import:CHIP-LED0805")
      (libsource (lib "eagle-import") (part "LEDCHIP-LED0805"))
    )
    (comp (ref "LED15")
      (value "orange")
      (footprint "eagle-import:CHIP-LED0805")
      (libsource (lib "eagle-import") (part "LEDCHIP-LED0805"))
    )
    (comp (ref "LED16")
      (value "yellow")
      (footprint "eagle-import:CHIP-LED0805")
      (libsource (lib "eagle-import") (part "LEDCHIP-LED0805"))
    )
    (comp (ref "LED17")
      (value "orange")
      (footprint "eagle-import:CHIP-LED0805")
      (libsource (lib "eagle-import") (part "LEDCHIP-LED0805"))
    )
    (comp (ref "R55")
      (value "220R")
      (footprint "eagle-import:R0805")
      (libsource (lib "eagle-import") (part "R-EU_R0805"))
    )
    (comp (ref "R56")
      (value "220R")
      (footprint "eagle-import:R0805")
      (libsource (lib "eagle-import") (part "R-EU_R0805"))
    )
    (comp (ref "R57")
      (value "220R")
      (footprint "eagle-import:R0805")
      (libsource (lib "eagle-import") (part "R-EU_R0805"))
    )
    (comp (ref "R58")
      (value "220R")
      (footprint "eagle-import:R0805")
      (libsource (lib "eagle-import") (part "R-EU_R0805"))
    )
    (comp (ref "X2")
      (value "M09HP")
      (footprint "eagle-import:M09HP")
      (libsource (lib "eagle-import") (part "M09HP"))
    )
    (comp (ref "IC2")
      (value "BTS555E3146")
      (footprint "eagle-import:TO220-52")
      (libsource (lib "eagle-import") (part "BTS555E3146"))
    )
    (comp (ref "Q2")
      (value "IRLZ44Z")
      (footprint "eagle-import:TO220BH")
      (libsource (lib "eagle-import") (part "IRLZ44Z"))
    )
    (comp (ref "R12")
      (value "2k2")
      (footprint "eagle-import:R0805")
      (libsource (lib "eagle-import") (part "R-EU_R0805"))
    )
    (comp (ref "T1")
      (value "BCR141")
      (footprint "eagle-import:SOT23-R_INFINEON")
      (libsource (lib "eagle-import") (part "BCR141"))
    )
    (comp (ref "C5")
      (value "1uF")
      (footprint "eagle-import:C0805")
      (libsource (lib "eagle-import") (part "C-EUC0805"))
    )
    (comp (ref "C6")
      (value "30pF")
      (footprint "eagle-import:C0805")
      (libsource (lib "eagle-import") (part "C-EUC0805"))
    )
    (comp (ref "C7")
      (value "30pF")
      (footprint "eagle-import:C0805")
      (libsource (lib "eagle-import") (part "C-EUC0805"))
    )
    (comp (ref "C8")
      (value "1uF")
      (footprint "eagle-import:C0805")
      (libsource (lib "eagle-import") (part "C-EUC0805"))
    )
    (comp (ref "C11")
      (value "1uF")
      (footprint "eagle-import:C0805")
      (libsource (lib "eagle-import") (part "C-EUC0805"))
    )
    (comp (ref "C13")
      (value "10uF")
      (footprint "eagle-import:E2-5")
      (libsource (lib "eagle-import") (part "CPOL-EUE2-5"))
    )
    (comp (ref "Q3")
      (value "16MHz")
      (footprint "eagle-import:HC49U-V")
      (libsource (lib "eagle-import") (part "CRYSTALHC49U-V"))
    )
    (comp (ref "R5")
      (value "1k")
      (footprint "eagle-import:R0805")
      (libsource (lib "eagle-import") (part "R-EU_R0805"))
    )
    (comp (ref "R17")
      (value "10k")
      (footprint "eagle-import:R0805")
      (libsource (lib "eagle-import") (part "R-EU_R0805"))
    )
    (comp (ref "R18")
      (value "10R")
      (footprint "eagle-import:R0805")
      (libsource (lib "eagle-import") (part "R-EU_R0805"))
    )
    (comp (ref "R19")
      (value "100k")
      (footprint "eagle-import:R0805")
      (libsource (lib "eagle-import") (part "R-EU_R0805"))
    )
    (comp (ref "R20")
      (value "100k")
      (footprint "eagle-import:R0805")
      (libsource (lib "eagle-import") (part "R-EU_R0805"))
    )
    (comp (ref "S2")
      (value "RST_NVM")
      (footprint "eagle-import:B3F-10XX")
      (fields (field (name "MPN") "B3F-1000"))
      (libsource (lib "eagle-import") (part "10-XX"))
    )
    (comp (ref "U$1")
      (value "STN1110-SOIC28")
      (footprint "eagle-import:SOIC28L")
      (libsource (lib "eagle-import") (part "STN1110-SOIC28"))
    )
    (comp (ref "CON1")
      (value "RIA-AKL-230-04")
      (footprint "eagle-import:CON-RIA-P4")
      (libsource (lib "eagle-import") (part "RIA-AKL-230-04"))
    )
    (comp (ref "CON2")
      (value "RIA-AKL-230-04")
      (footprint "eagle-import:CON-RIA-P4")
      (libsource (lib "eagle-import") (part "RIA-AKL-230-04"))
    )
    (comp (ref "CON3")
      (value "RIA-AKL-230-03")
      (footprint "eagle-import:CON-RIA-P3")
      (libsource (lib "eagle-import") (part "RIA-AKL-230-03"))
    )
    (comp (ref "R59")
      (value "10k")
      (footprint "eagle-import:R0805")
      (libsource (lib "eagle-import") (part "R-EU_R0805"))
    )
    (comp (ref "R60")
      (value "10k")
      (footprint "eagle-import:R0805")
      (libsource (lib "eagle-import") (part "R-EU_R0805"))
    )
    (comp (ref "R61")
      (value "10k")
      (footprint "eagle-import:R0805")
      (libsource (lib "eagle-import") (part "R-EU_R0805"))
    )
    (comp (ref "R62")
      (value "10k")
      (footprint "eagle-import:R0805")
      (libsource (lib "eagle-import") (part "R-EU_R0805"))
    )
    (comp (ref "R63")
      (value "510R 0W5")
      (footprint "eagle-import:0207_12")
      (libsource (lib "eagle-import") (part "R-EU_0207/12"))
    )
    (comp (ref "R64")
      (value "1k")
      (footprint "eagle-import:R0805")
      (libsource (lib "eagle-import") (part "R-EU_R0805"))
    )
    (comp (ref "R65")
      (value "510R 0W5")
      (footprint "eagle-import:0207_12")
      (libsource (lib "eagle-import") (part "R-EU_0207/12"))
    )
    (comp (ref "R66")
      (value "1k")
      (footprint "eagle-import:R0805")
      (libsource (lib "eagle-import") (part "R-EU_R0805"))
    )
    (comp (ref "T8")
      (value "MMBT3904")
      (footprint "eagle-import:SOT23-BEC")
      (libsource (lib "eagle-import") (part "-NPN-SOT23-BECMMBT3904LT1"))
    )
    (comp (ref "T9")
      (value "MMBT3904")
      (footprint "eagle-import:SOT23-BEC")
      (libsource (lib "eagle-import") (part "-NPN-SOT23-BECBC817-16"))
    )
  )
  (nets
    (net (code "1") (name "+3V3") (class "Default")
      (node (ref "C10") (pin "+") (pinfunction "+_+") (pintype "passive"))
      (node (ref "C19") (pin "1") (pinfunction "1_1") (pintype "passive"))
      (node (ref "C2") (pin "1") (pinfunction "1_1") (pintype "passive"))
      (node (ref "C5") (pin "2") (pinfunction "2_2") (pintype "passive"))
      (node (ref "IC1") (pin "20") (pinfunction "AVCC_20") (pintype "power_in"))
      (node (ref "IC1") (pin "21") (pinfunction "AREF_21") (pintype "passive"))
      (node (ref "IC1") (pin "7") (pinfunction "VCC_7") (pintype "power_in"))
      (node (ref "IC4") (pin "4") (pinfunction "FB_4") (pintype "input"))
      (node (ref "JP2") (pin "1") (pinfunction "1_1") (pintype "passive"))
      (node (ref "L1") (pin "P$2") (pinfunction "2_P$2") (pintype "passive"))
      (node (ref "LED8") (pin "A") (pinfunction "A_A") (pintype "passive"))
      (node (ref "R1") (pin "2") (pinfunction "2_2") (pintype "passive"))
      (node (ref "R14") (pin "2") (pinfunction "2_2") (pintype "passive"))
      (node (ref "R17") (pin "2") (pinfunction "2_2") (pintype "passive"))
      (node (ref "R18") (pin "1") (pinfunction "1_1") (pintype "passive"))
      (node (ref "R19") (pin "1") (pinfunction "1_1") (pintype "passive"))
      (node (ref "R2") (pin "2") (pinfunction "2_2") (pintype "passive"))
      (node (ref "R3") (pin "2") (pinfunction "2_2") (pintype "passive"))
      (node (ref "R4") (pin "2") (pinfunction "2_2") (pintype "passive"))
      (node (ref "R5") (pin "2") (pinfunction "2_2") (pintype "passive"))
      (node (ref "R55") (pin "1") (pinfunction "1_1") (pintype "passive"))
      (node (ref "R56") (pin "1") (pinfunction "1_1") (pintype "passive"))
      (node (ref "R57") (pin "1") (pinfunction "1_1") (pintype "passive"))
      (node (ref "R58") (pin "1") (pinfunction "1_1") (pintype "passive"))
      (node (ref "R62") (pin "1") (pinfunction "1_1") (pintype "passive"))
      (node (ref "R69") (pin "2") (pinfunction "2_2") (pintype "passive"))
      (node (ref "R75") (pin "1") (pinfunction "1_1") (pintype "passive"))
      (node (ref "R82") (pin "1") (pinfunction "1_1") (pintype "passive"))
      (node (ref "S1") (pin "1") (pinfunction "S_1") (pintype "passive"))
      (node (ref "S1") (pin "2") (pinfunction "S1_2") (pintype "passive"))
      (node (ref "T3") (pin "3") (pinfunction "C_3") (pintype "passive"))
      (node (ref "T3") (pin "6") (pinfunction "C_6") (pintype "passive"))
      (node (ref "U$1") (pin "13") (pinfunction "VDD_13") (pintype "bidirectional"))
      (node (ref "U1") (pin "12") (pinfunction "3V3_12") (pintype "bidirectional"))
      (node (ref "U3") (pin "5") (pinfunction "VIO_5") (pintype "power_in"))
    )
    (net (code "2") (name "+5V") (class "Default")
      (node (ref "C15") (pin "+") (pinfunction "+_+") (pintype "passive"))
      (node (ref "C26") (pin "1") (pinfunction "1_1") (pintype "passive"))
      (node (ref "D18") (pin "1") (pinfunction "A_1") (pintype "passive"))
      (node (ref "IC5") (pin "4") (pinfunction "FB_4") (pintype "input"))
      (node (ref "JP5") (pin "1") (pinfunction "1_1") (pintype "passive"))
      (node (ref "L2") (pin "P$2") (pinfunction "2_P$2") (pintype "passive"))
      (node (ref "LED13") (pin "A") (pinfunction "A_A") (pintype "passive"))
      (node (ref "R80") (pin "1") (pinfunction "1_1") (pintype "passive"))
      (node (ref "U3") (pin "3") (pinfunction "VDD_3") (pintype "power_in"))
    )
    (net (code "3") (name "+12V") (class "Default")
      (node (ref "C12") (pin "1") (pinfunction "1_1") (pintype "passive"))
      (node (ref "C14") (pin "+") (pinfunction "+_+") (pintype "passive"))
      (node (ref "C16") (pin "1") (pinfunction "1_1") (pintype "passive"))
      (node (ref "C27") (pin "1") (pinfunction "1_1") (pintype "passive"))
      (node (ref "C9") (pin "+") (pinfunction "+_+") (pintype "passive"))
      (node (ref "IC10") (pin "3") (pinfunction "IN_3") (pintype "input"))
      (node (ref "IC4") (pin "1") (pinfunction "VIN_1") (pintype "power_in"))
      (node (ref "IC5") (pin "1") (pinfunction "VIN_1") (pintype "power_in"))
      (node (ref "IC9") (pin "3") (pinfunction "V+_3") (pintype "power_in"))
      (node (ref "JP3") (pin "1") (pinfunction "1_1") (pintype "passive"))
      (node (ref "Q4") (pin "5") (pinfunction "D_5") (pintype "passive"))
      (node (ref "Q4") (pin "6") (pinfunction "D_6") (pintype "passive"))
      (node (ref "Q4") (pin "7") (pinfunction "D_7") (pintype "passive"))
      (node (ref "Q4") (pin "8") (pinfunction "D_8") (pintype "passive"))
      (node (ref "R12") (pin "2") (pinfunction "2_2") (pintype "passive"))
      (node (ref "R59") (pin "1") (pinfunction "1_1") (pintype "passive"))
      (node (ref "R63") (pin "1") (pinfunction "1_1") (pintype "passive"))
      (node (ref "R65") (pin "1") (pinfunction "1_1") (pintype "passive"))
    )
    (net (code "4") (name "+12V_RAW") (class "Default")
      (node (ref "C17") (pin "1") (pinfunction "1_1") (pintype "passive"))
      (node (ref "D7") (pin "A") (pinfunction "A_A") (pintype "passive"))
      (node (ref "JP1") (pin "2") (pinfunction "2_2") (pintype "passive"))
    )
    (net (code "5") (name "12V_OUT") (class "Default")
      (node (ref "CON2") (pin "P$4") (pinfunction "P$4_P$4") (pintype "bidirectional"))
      (node (ref "IC2") (pin "1") (pinfunction "O1_1") (pintype "passive"))
      (node (ref "IC2") (pin "5") (pinfunction "O2_5") (pintype "passive"))
      (node (ref "Q2") (pin "S") (pinfunction "S_S") (pintype "passive"))
    )
    (net (code "6") (name "ANALOG_IN") (class "Default")
      (node (ref "U$1") (pin "2") (pinfunction "ANALOG_IN_2") (pintype "bidirectional"))
    )
    (net (code "7") (name "CAN_RX") (class "Default")
      (node (ref "U$1") (pin "14") (pinfunction "CAN_RX_14") (pintype "bidirectional"))
      (node (ref "U3") (pin "4") (pinfunction "RXD_4") (pintype "output"))
    )
    (net (code "8") (name "CAN_TX") (class "Default")
      (node (ref "U$1") (pin "15") (pinfunction "CAN_TX_15") (pintype "bidirectional"))
      (node (ref "U3") (pin "1") (pinfunction "TXD_1") (pintype "input"))
    )
    (net (code "9") (name "GND") (class "Default")
      (node (ref "C1") (pin "2") (pinfunction "2_2") (pintype "passive"))
      (node (ref "C10") (pin "-") (pinfunction "-_-") (pintype "passive"))
      (node (ref "C11") (pin "2") (pinfunction "2_2") (pintype "passive"))
      (node (ref "C12") (pin "2") (pinfunction "2_2") (pintype "passive"))
      (node (ref "C13") (pin "-") (pinfunction "-_-") (pintype "passive"))
      (node (ref "C14") (pin "-") (pinfunction "-_-") (pintype "passive"))
      (node (ref "C15") (pin "-") (pinfunction "-_-") (pintype "passive"))
      (node (ref "C16") (pin "2") (pinfunction "2_2") (pintype "passive"))
      (node (ref "C17") (pin "2") (pinfunction "2_2") (pintype "passive"))
      (node (ref "C18") (pin "2") (pinfunction "2_2") (pintype "passive"))
      (node (ref "C19") (pin "2") (pinfunction "2_2") (pintype "passive"))
      (node (ref "C2") (pin "2") (pinfunction "2_2") (pintype "passive"))
      (node (ref "C24") (pin "2") (pinfunction "2_2") (pintype "passive"))
      (node (ref "C25") (pin "2") (pinfunction "2_2") (pintype "passive"))
      (node (ref "C26") (pin "2") (pinfunction "2_2") (pintype "passive"))
      (node (ref "C27") (pin "2") (pinfunction "2_2") (pintype "passive"))
      (node (ref "C3") (pin "1") (pinfunction "1_1") (pintype "passive"))
      (node (ref "C4") (pin "1") (pinfunction "1_1") (pintype "passive"))
      (node (ref "C5") (pin "1") (pinfunction "1_1") (pintype "passive"))
      (node (ref "C6") (pin "2") (pinfunction "2_2") (pintype "passive"))
      (node (ref "C7") (pin "2") (pinfunction "2_2") (pintype "passive"))
      (node (ref "C8") (pin "2") (pinfunction "2_2") (pintype "passive"))
      (node (ref "C9") (pin "-") (pinfunction "-_-") (pintype "passive"))
      (node (ref "CON3") (pin "P$1") (pinfunction "P$1_P$1") (pintype "bidirectional"))
      (node (ref "CON3") (pin "P$2") (pinfunction "P$2_P$2") (pintype "bidirectional"))
      (node (ref "D1") (pin "A") (pinfunction "A_A") (pintype "passive"))
      (node (ref "D13") (pin "1") (pinfunction "1_1") (pintype "passive"))
      (node (ref "D13") (pin "3") (pinfunction "3_3") (pintype "passive"))
      (node (ref "D14") (pin "3") (pinfunction "AA_3") (pintype "passive"))
      (node (ref "D15") (pin "3") (pinfunction "AA_3") (pintype "passive"))
      (node (ref "D17") (pin "3") (pinfunction "C_3") (pintype "passive"))
      (node (ref "D2") (pin "A") (pinfunction "A_A") (pintype "passive"))
      (node (ref "D6") (pin "A") (pinfunction "A_A") (pintype "passive"))
      (node (ref "D8") (pin "A") (pinfunction "A_A") (pintype "passive"))
      (node (ref "IC1") (pin "22") (pinfunction "GND_22") (pintype "power_in"))
      (node (ref "IC1") (pin "8") (pinfunction "GND_8") (pintype "power_in"))
      (node (ref "IC4") (pin "3") (pinfunction "GND_3") (pintype "power_in"))
      (node (ref "IC4") (pin "5") (pinfunction "OFF_5") (pintype "input"))
      (node (ref "IC5") (pin "3") (pinfunction "GND_3") (pintype "power_in"))
      (node (ref "IC5") (pin "5") (pinfunction "OFF_5") (pintype "input"))
      (node (ref "IC9") (pin "12") (pinfunction "GND_12") (pintype "power_in"))
      (node (ref "JP4") (pin "1") (pinfunction "1_1") (pintype "passive"))
      (node (ref "Q5") (pin "2") (pinfunction "S_2") (pintype "passive"))
      (node (ref "Q8") (pin "2") (pinfunction "S_2") (pintype "passive"))
      (node (ref "R10") (pin "1") (pinfunction "1_1") (pintype "passive"))
      (node (ref "R11") (pin "1") (pinfunction "1_1") (pintype "passive"))
      (node (ref "R15") (pin "1") (pinfunction "1_1") (pintype "passive"))
      (node (ref "R16") (pin "1") (pinfunction "1_1") (pintype "passive"))
      (node (ref "R20") (pin "1") (pinfunction "1_1") (pintype "passive"))
      (node (ref "R25") (pin "1") (pinfunction "1_1") (pintype "passive"))
      (node (ref "R28") (pin "1") (pinfunction "1_1") (pintype "passive"))
      (node (ref "R6") (pin "1") (pinfunction "1_1") (pintype "passive"))
      (node (ref "R60") (pin "2") (pinfunction "2_2") (pintype "passive"))
      (node (ref "R7") (pin "1") (pinfunction "1_1") (pintype "passive"))
      (node (ref "R72") (pin "1") (pinfunction "1_1") (pintype "passive"))
      (node (ref "R78") (pin "1") (pinfunction "1_1") (pintype "passive"))
      (node (ref "R8") (pin "1") (pinfunction "1_1") (pintype "passive"))
      (node (ref "R81") (pin "2") (pinfunction "2_2") (pintype "passive"))
      (node (ref "R9") (pin "1") (pinfunction "1_1") (pintype "passive"))
      (node (ref "S2") (pin "3") (pinfunction "P_3") (pintype "passive"))
      (node (ref "SV1") (pin "6") (pinfunction "6_6") (pintype "passive"))
      (node (ref "T1") (pin "2") (pinfunction "E_2") (pintype "passive"))
      (node (ref "T11") (pin "2") (pinfunction "E_2") (pintype "passive"))
      (node (ref "T8") (pin "E") (pinfunction "E_E") (pintype "passive"))
      (node (ref "T9") (pin "E") (pinfunction "E_E") (pintype "passive"))
      (node (ref "U$1") (pin "19") (pinfunction "VSS_19") (pintype "bidirectional"))
      (node (ref "U$1") (pin "27") (pinfunction "AVSS_27") (pintype "bidirectional"))
      (node (ref "U$1") (pin "8") (pinfunction "VSS_8") (pintype "bidirectional"))
      (node (ref "U1") (pin "13") (pinfunction "GND_13") (pintype "bidirectional"))
      (node (ref "U1") (pin "21") (pinfunction "GND1_21") (pintype "bidirectional"))
      (node (ref "U1") (pin "22") (pinfunction "GND2_22") (pintype "bidirectional"))
      (node (ref "U3") (pin "2") (pinfunction "VSS_2") (pintype "power_in"))
      (node (ref "X2") (pin "1") (pinfunction "1_1") (pintype "passive"))
      (node (ref "X2") (pin "2") (pinfunction "2_2") (pintype "passive"))
    )
    (net (code "10") (name "HC05_RST") (class "Default")
      (node (ref "IC1") (pin "14") (pinfunction "PB0(ICP)_14") (pintype "bidirectional"))
      (node (ref "U1") (pin "11") (pinfunction "RST_11") (pintype "bidirectional"))
    )
    (net (code "11") (name "HS_CAN_HI") (class "Default")
      (node (ref "R67") (pin "2") (pinfunction "2_2") (pintype "passive"))
      (node (ref "U3") (pin "7") (pinfunction "CANH_7") (pintype "input"))
      (node (ref "X2") (pin "3") (pinfunction "3_3") (pintype "passive"))
    )
    (net (code "12") (name "HS_CAN_LO") (class "Default")
      (node (ref "D13") (pin "2") (pinfunction "2_2") (pintype "passive"))
      (node (ref "R68") (pin "2") (pinfunction "2_2") (pintype "passive"))
      (node (ref "U3") (pin "6") (pinfunction "CANL_6") (pintype "input"))
      (node (ref "X2") (pin "5") (pinfunction "5_5") (pintype "passive"))
    )
    (net (code "13") (name "IGN0") (class "Default")
      (node (ref "CON1") (pin "P$3") (pinfunction "P$3_P$3") (pintype "bidirectional"))
      (node (ref "CON2") (pin "P$3") (pinfunction "P$3_P$3") (pintype "bidirectional"))
      (node (ref "R13") (pin "2") (pinfunction "2_2") (pintype "passive"))
    )
    (net (code "14") (name "IGN1") (class "Default")
      (node (ref "CON1") (pin "P$2") (pinfunction "P$2_P$2") (pintype "bidirectional"))
      (node (ref "CON2") (pin "P$2") (pinfunction "P$2_P$2") (pintype "bidirectional"))
    )
    (net (code "15") (name "IGN2") (class "Default")
      (node (ref "CON1") (pin "P$1") (pinfunction "P$1_P$1") (pintype "bidirectional"))
      (node (ref "CON2") (pin "P$1") (pinfunction "P$1_P$1") (pintype "bidirectional"))
    )
    (net (code "16") (name "IGN_CTL") (class "Default")
      (node (ref "IC1") (pin "13") (pinfunction "PD7(AIN1)_13") (pintype "bidirectional"))
      (node (ref "T1") (pin "1") (pinfunction "B_1") (pintype "passive"))
    )
    (net (code "17") (name "J1850_BUS+") (class "Default")
      (node (ref "D15") (pin "2") (pinfunction "K2_2") (pintype "passive"))
      (node (ref "D16") (pin "3") (pinfunction "C_3") (pintype "passive"))
      (node (ref "R73") (pin "2") (pinfunction "2_2") (pintype "passive"))
      (node (ref "R76") (pin "2") (pinfunction "2_2") (pintype "passive"))
      (node (ref "R79") (pin "2") (pinfunction "2_2") (pintype "passive"))
      (node (ref "X2") (pin "7") (pinfunction "7_7") (pintype "passive"))
    )
    (net (code "18") (name "J1850_BUS+_TX") (class "Default")
      (node (ref "Q8") (pin "1") (pinfunction "G_1") (pintype "passive"))
      (node (ref "R78") (pin "2") (pinfunction "2_2") (pintype "passive"))
      (node (ref "U$1") (pin "6") (pinfunction "J1850_BUS+TX_6") (pintype "bidirectional"))
    )
    (net (code "19") (name "J1850_BUS-") (class "Default")
      (node (ref "D15") (pin "1") (pinfunction "K1_1") (pintype "passive"))
      (node (ref "R74") (pin "2") (pinfunction "2_2") (pintype "passive"))
      (node (ref "R83") (pin "1") (pinfunction "1_1") (pintype "passive"))
      (node (ref "T11") (pin "3") (pinfunction "C_3") (pintype "passive"))
      (node (ref "X2") (pin "6") (pinfunction "6_6") (pintype "passive"))
    )
    (net (code "20") (name "KL15") (class "Default")
      (node (ref "CON1") (pin "P$4") (pinfunction "P$4_P$4") (pintype "bidirectional"))
      (node (ref "IC2") (pin "3") (pinfunction "VBB_3") (pintype "passive"))
      (node (ref "JP1") (pin "1") (pinfunction "1_1") (pintype "passive"))
      (node (ref "Q2") (pin "D") (pinfunction "D_D") (pintype "passive"))
    )
    (net (code "21") (name "KL30") (class "Default")
      (node (ref "JP1") (pin "3") (pinfunction "3_3") (pintype "passive"))
      (node (ref "X2") (pin "9") (pinfunction "9_9") (pintype "passive"))
    )
    (net (code "22") (name "K_LINE") (class "Default")
      (node (ref "D14") (pin "2") (pinfunction "K2_2") (pintype "passive"))
      (node (ref "R61") (pin "1") (pinfunction "1_1") (pintype "passive"))
      (node (ref "R63") (pin "2") (pinfunction "2_2") (pintype "passive"))
      (node (ref "T8") (pin "C") (pinfunction "C_C") (pintype "passive"))
      (node (ref "X2") (pin "4") (pinfunction "4_4") (pintype "passive"))
    )
    (net (code "23") (name "L_LINE") (class "Default")
      (node (ref "D14") (pin "1") (pinfunction "K1_1") (pintype "passive"))
      (node (ref "R65") (pin "2") (pinfunction "2_2") (pintype "passive"))
      (node (ref "T9") (pin "C") (pinfunction "C_C") (pintype "passive"))
      (node (ref "X2") (pin "8") (pinfunction "8_8") (pintype "passive"))
    )
    (net (code "24") (name "MISO") (class "Default")
      (node (ref "IC1") (pin "18") (pinfunction "PB4(MISO)_18") (pintype "bidirectional"))
      (node (ref "SV1") (pin "1") (pinfunction "1_1") (pintype "passive"))
    )
    (net (code "25") (name "MODE_KEY") (class "Default")
      (node (ref "R7") (pin "2") (pinfunction "2_2") (pintype "passive"))
      (node (ref "U1") (pin "34") (pinfunction "PIO11_34") (pintype "bidirectional"))
    )
    (net (code "26") (name "MOSI") (class "Default")
      (node (ref "IC1") (pin "17") (pinfunction "PB3(MOSI/OC2)_17") (pintype "bidirectional"))
      (node (ref "SV1") (pin "4") (pinfunction "4_4") (pintype "passive"))
    )
    (net (code "27") (name "Net-(C24-Pad1)") (class "Default")
      (node (ref "C24") (pin "1") (pinfunction "1_1") (pintype "passive"))
      (node (ref "R67") (pin "1") (pinfunction "1_1") (pintype "passive"))
    )
    (net (code "28") (name "Net-(C25-Pad1)") (class "Default")
      (node (ref "C25") (pin "1") (pinfunction "1_1") (pintype "passive"))
      (node (ref "R68") (pin "1") (pinfunction "1_1") (pintype "passive"))
    )
    (net (code "29") (name "Net-(D7-PadC)") (class "Default")
      (node (ref "D7") (pin "C") (pinfunction "C_C") (pintype "passive"))
      (node (ref "D9") (pin "C") (pinfunction "C_C") (pintype "passive"))
      (node (ref "Q4") (pin "1") (pinfunction "S_1") (pintype "passive"))
      (node (ref "Q4") (pin "2") (pinfunction "S_2") (pintype "passive"))
      (node (ref "Q4") (pin "3") (pinfunction "S_3") (pintype "passive"))
      (node (ref "R26") (pin "2") (pinfunction "2_2") (pintype "passive"))
      (node (ref "T2") (pin "E") (pinfunction "E_E") (pintype "passive"))
    )
    (net (code "30") (name "Net-(D8-PadC)") (class "Default")
      (node (ref "D8") (pin "C") (pinfunction "C_C") (pintype "passive"))
      (node (ref "R26") (pin "1") (pinfunction "1_1") (pintype "passive"))
      (node (ref "R27") (pin "2") (pinfunction "2_2") (pintype "passive"))
    )
    (net (code "31") (name "Net-(D16-A)") (class "Default")
      (node (ref "D16") (pin "1") (pinfunction "A_1") (pintype "passive"))
      (node (ref "Q7") (pin "3") (pinfunction "D_3") (pintype "passive"))
    )
    (net (code "32") (name "Net-(D17-A)") (class "Default")
      (node (ref "D17") (pin "1") (pinfunction "A_1") (pintype "passive"))
      (node (ref "R76") (pin "1") (pinfunction "1_1") (pintype "passive"))
    )
    (net (code "33") (name "Net-(D18-C)") (class "Default")
      (node (ref "D18") (pin "3") (pinfunction "C_3") (pintype "passive"))
      (node (ref "R83") (pin "2") (pinfunction "2_2") (pintype "passive"))
    )
    (net (code "34") (name "Net-(IC1-PB6(XTAL1{slash}TOSC1))") (class "Default")
      (node (ref "C3") (pin "2") (pinfunction "2_2") (pintype "passive"))
      (node (ref "IC1") (pin "9") (pinfunction "PB6(XTAL1/TOSC1)_9") (pintype "bidirectional"))
      (node (ref "Q1") (pin "1") (pinfunction "1_1") (pintype "passive"))
    )
    (net (code "35") (name "Net-(IC1-PB7(XTAL2{slash}TOSC2))") (class "Default")
      (node (ref "C4") (pin "2") (pinfunction "2_2") (pintype "passive"))
      (node (ref "IC1") (pin "10") (pinfunction "PB7(XTAL2/TOSC2)_10") (pintype "bidirectional"))
      (node (ref "Q1") (pin "2") (pinfunction "2_2") (pintype "passive"))
    )
    (net (code "36") (name "Net-(IC1-PC0(ADC0))") (class "Default")
      (node (ref "IC1") (pin "23") (pinfunction "PC0(ADC0)_23") (pintype "bidirectional"))
      (node (ref "LED1") (pin "C") (pinfunction "C_C") (pintype "passive"))
    )
    (net (code "37") (name "Net-(IC1-PC1(ADC1))") (class "Default")
      (node (ref "IC1") (pin "24") (pinfunction "PC1(ADC1)_24") (pintype "bidirectional"))
      (node (ref "LED2") (pin "C") (pinfunction "C_C") (pintype "passive"))
    )
    (net (code "38") (name "Net-(IC1-PC2(ADC2))") (class "Default")
      (node (ref "IC1") (pin "25") (pinfunction "PC2(ADC2)_25") (pintype "bidirectional"))
      (node (ref "LED3") (pin "C") (pinfunction "C_C") (pintype "passive"))
    )
    (net (code "39") (name "Net-(IC1-PC5(ADC5{slash}SCL))") (class "Default")
      (node (ref "IC1") (pin "28") (pinfunction "PC5(ADC5/SCL)_28") (pintype "bidirectional"))
      (node (ref "R6") (pin "2") (pinfunction "2_2") (pintype "passive"))
      (node (ref "S1") (pin "3") (pinfunction "P_3") (pintype "passive"))
      (node (ref "S1") (pin "4") (pinfunction "P1_4") (pintype "passive"))
    )
    (net (code "40") (name "Net-(IC2-IN)") (class "Default")
      (node (ref "IC2") (pin "2") (pinfunction "IN_2") (pintype "input"))
      (node (ref "Q2") (pin "G") (pinfunction "G_G") (pintype "passive"))
      (node (ref "R12") (pin "1") (pinfunction "1_1") (pintype "passive"))
      (node (ref "T1") (pin "3") (pinfunction "C_3") (pintype "passive"))
    )
    (net (code "41") (name "Net-(IC4-OUT)") (class "Default")
      (node (ref "D1") (pin "C") (pinfunction "C_C") (pintype "passive"))
      (node (ref "IC4") (pin "2") (pinfunction "OUT_2") (pintype "output"))
      (node (ref "L1") (pin "P$1") (pinfunction "1_P$1") (pintype "passive"))
    )
    (net (code "42") (name "Net-(IC5-OUT)") (class "Default")
      (node (ref "D6") (pin "C") (pinfunction "C_C") (pintype "passive"))
      (node (ref "IC5") (pin "2") (pinfunction "OUT_2") (pintype "output"))
      (node (ref "L2") (pin "P$1") (pinfunction "1_P$1") (pintype "passive"))
    )
    (net (code "43") (name "Net-(IC9A-+IN)") (class "Default")
      (node (ref "IC9") (pin "5") (pinfunction "+IN_5") (pintype "input"))
      (node (ref "R59") (pin "2") (pinfunction "2_2") (pintype "passive"))
      (node (ref "R60") (pin "1") (pinfunction "1_1") (pintype "passive"))
    )
    (net (code "44") (name "Net-(IC9A--IN)") (class "Default")
      (node (ref "IC9") (pin "4") (pinfunction "-IN_4") (pintype "input"))
      (node (ref "R61") (pin "2") (pinfunction "2_2") (pintype "passive"))
    )
    (net (code "45") (name "Net-(IC9B-+IN)") (class "Default")
      (node (ref "IC9") (pin "7") (pinfunction "+IN_7") (pintype "input"))
      (node (ref "R73") (pin "1") (pinfunction "1_1") (pintype "passive"))
    )
    (net (code "46") (name "Net-(IC9B--IN)") (class "Default")
      (node (ref "IC9") (pin "6") (pinfunction "-IN_6") (pintype "input"))
      (node (ref "R74") (pin "1") (pinfunction "1_1") (pintype "passive"))
    )
    (net (code "47") (name "Net-(IC9C-+IN)") (class "Default")
      (node (ref "IC9") (pin "9") (pinfunction "+IN_9") (pintype "input"))
      (node (ref "R79") (pin "1") (pinfunction "1_1") (pintype "passive"))
    )
    (net (code "48") (name "Net-(IC9C--IN)") (class "Default")
      (node (ref "IC9") (pin "8") (pinfunction "-IN_8") (pintype "input"))
      (node (ref "R80") (pin "2") (pinfunction "2_2") (pintype "passive"))
      (node (ref "R81") (pin "1") (pinfunction "1_1") (pintype "passive"))
    )
    (net (code "49") (name "Net-(IC10-ADJ)") (class "Default")
      (node (ref "IC10") (pin "1") (pinfunction "ADJ_1") (pintype "input"))
      (node (ref "R70") (pin "1") (pinfunction "1_1") (pintype "passive"))
      (node (ref "R71") (pin "2") (pinfunction "2_2") (pintype "passive"))
    )
    (net (code "50") (name "Net-(LED1-PadA)") (class "Default")
      (node (ref "LED1") (pin "A") (pinfunction "A_A") (pintype "passive"))
      (node (ref "R2") (pin "1") (pinfunction "1_1") (pintype "passive"))
    )
    (net (code "51") (name "Net-(LED2-PadA)") (class "Default")
      (node (ref "LED2") (pin "A") (pinfunction "A_A") (pintype "passive"))
      (node (ref "R3") (pin "1") (pinfunction "1_1") (pintype "passive"))
    )
    (net (code "52") (name "Net-(LED3-PadA)") (class "Default")
      (node (ref "LED3") (pin "A") (pinfunction "A_A") (pintype "passive"))
      (node (ref "R4") (pin "1") (pinfunction "1_1") (pintype "passive"))
    )
    (net (code "53") (name "Net-(LED4-PadC)") (class "Default")
      (node (ref "LED4") (pin "C") (pinfunction "C_C") (pintype "passive"))
      (node (ref "R10") (pin "2") (pinfunction "2_2") (pintype "passive"))
    )
    (net (code "54") (name "Net-(LED5-PadC)") (class "Default")
      (node (ref "LED5") (pin "C") (pinfunction "C_C") (pintype "passive"))
      (node (ref "R15") (pin "2") (pinfunction "2_2") (pintype "passive"))
    )
    (net (code "55") (name "Net-(LED6-PadC)") (class "Default")
      (node (ref "LED6") (pin "C") (pinfunction "C_C") (pintype "passive"))
      (node (ref "R9") (pin "2") (pinfunction "2_2") (pintype "passive"))
    )
    (net (code "56") (name "Net-(LED7-PadC)") (class "Default")
      (node (ref "LED7") (pin "C") (pinfunction "C_C") (pintype "passive"))
      (node (ref "R8") (pin "2") (pinfunction "2_2") (pintype "passive"))
    )
    (net (code "57") (name "Net-(LED8-PadC)") (class "Default")
      (node (ref "LED8") (pin "C") (pinfunction "C_C") (pintype "passive"))
      (node (ref "R16") (pin "2") (pinfunction "2_2") (pintype "passive"))
    )
    (net (code "58") (name "Net-(LED13-PadC)") (class "Default")
      (node (ref "LED13") (pin "C") (pinfunction "C_C") (pintype "passive"))
      (node (ref "R25") (pin "2") (pinfunction "2_2") (pintype "passive"))
    )
    (net (code "59") (name "Net-(LED14-PadA)") (class "Default")
      (node (ref "LED14") (pin "A") (pinfunction "A_A") (pintype "passive"))
      (node (ref "R58") (pin "2") (pinfunction "2_2") (pintype "passive"))
    )
    (net (code "60") (name "Net-(LED15-PadA)") (class "Default")
      (node (ref "LED15") (pin "A") (pinfunction "A_A") (pintype "passive"))
      (node (ref "R57") (pin "2") (pinfunction "2_2") (pintype "passive"))
    )
    (net (code "61") (name "Net-(LED16-PadA)") (class "Default")
      (node (ref "LED16") (pin "A") (pinfunction "A_A") (pintype "passive"))
      (node (ref "R56") (pin "2") (pinfunction "2_2") (pintype "passive"))
    )
    (net (code "62") (name "Net-(LED17-PadA)") (class "Default")
      (node (ref "LED17") (pin "A") (pinfunction "A_A") (pintype "passive"))
      (node (ref "R55") (pin "2") (pinfunction "2_2") (pintype "passive"))
    )
    (net (code "63") (name "Net-(Q4-G)") (class "Default")
      (node (ref "C18") (pin "1") (pinfunction "1_1") (pintype "passive"))
      (node (ref "D9") (pin "A") (pinfunction "A_A") (pintype "passive"))
      (node (ref "Q4") (pin "4") (pinfunction "G_4") (pintype "passive"))
      (node (ref "R28") (pin "2") (pinfunction "2_2") (pintype "passive"))
      (node (ref "T2") (pin "C") (pinfunction "C_C") (pintype "passive"))
    )
    (net (code "64") (name "Net-(Q5-D)") (class "Default")
      (node (ref "Q5") (pin "3") (pinfunction "D_3") (pintype "passive"))
      (node (ref "R71") (pin "1") (pinfunction "1_1") (pintype "passive"))
      (node (ref "R72") (pin "2") (pinfunction "2_2") (pintype "passive"))
    )
    (net (code "65") (name "Net-(Q7-G)") (class "Default")
      (node (ref "Q7") (pin "1") (pinfunction "G_1") (pintype "passive"))
      (node (ref "Q8") (pin "3") (pinfunction "D_3") (pintype "passive"))
      (node (ref "R77") (pin "1") (pinfunction "1_1") (pintype "passive"))
    )
    (net (code "66") (name "Net-(R27-Pad1)") (class "Default")
      (node (ref "R27") (pin "1") (pinfunction "1_1") (pintype "passive"))
      (node (ref "T2") (pin "B") (pinfunction "B_B") (pintype "passive"))
    )
    (net (code "67") (name "Net-(R64-Pad2)") (class "Default")
      (node (ref "R64") (pin "2") (pinfunction "2_2") (pintype "passive"))
      (node (ref "T8") (pin "B") (pinfunction "B_B") (pintype "passive"))
    )
    (net (code "68") (name "Net-(R66-Pad2)") (class "Default")
      (node (ref "R66") (pin "2") (pinfunction "2_2") (pintype "passive"))
      (node (ref "T9") (pin "B") (pinfunction "B_B") (pintype "passive"))
    )
    (net (code "69") (name "Net-(T3A-E)") (class "Default")
      (node (ref "LED4") (pin "A") (pinfunction "A_A") (pintype "passive"))
      (node (ref "T3") (pin "1") (pinfunction "E_1") (pintype "passive"))
    )
    (net (code "70") (name "Net-(T3B-E)") (class "Default")
      (node (ref "LED5") (pin "A") (pinfunction "A_A") (pintype "passive"))
      (node (ref "T3") (pin "4") (pinfunction "E_4") (pintype "passive"))
    )
    (net (code "71") (name "Net-(T11-B)") (class "Default")
      (node (ref "R84") (pin "1") (pinfunction "1_1") (pintype "passive"))
      (node (ref "T11") (pin "1") (pinfunction "B_1") (pintype "passive"))
    )
    (net (code "72") (name "Net-(U$1-AVDD)") (class "Default")
      (node (ref "C11") (pin "1") (pinfunction "1_1") (pintype "passive"))
      (node (ref "R18") (pin "2") (pinfunction "2_2") (pintype "passive"))
      (node (ref "U$1") (pin "28") (pinfunction "AVDD_28") (pintype "bidirectional"))
    )
    (net (code "73") (name "Net-(U$1-OSC1)") (class "Default")
      (node (ref "C7") (pin "1") (pinfunction "1_1") (pintype "passive"))
      (node (ref "Q3") (pin "2") (pinfunction "2_2") (pintype "passive"))
      (node (ref "U$1") (pin "9") (pinfunction "OSC1_9") (pintype "bidirectional"))
    )
    (net (code "74") (name "Net-(U$1-OSC2)") (class "Default")
      (node (ref "C6") (pin "1") (pinfunction "1_1") (pintype "passive"))
      (node (ref "Q3") (pin "1") (pinfunction "1_1") (pintype "passive"))
      (node (ref "U$1") (pin "10") (pinfunction "OSC2_10") (pintype "bidirectional"))
    )
    (net (code "75") (name "Net-(U$1-PWR_CTRL)") (class "Default")
      (node (ref "R20") (pin "2") (pinfunction "2_2") (pintype "passive"))
      (node (ref "U$1") (pin "18") (pinfunction "PWR_CTRL_18") (pintype "bidirectional"))
    )
    (net (code "76") (name "Net-(U$1-VCAP)") (class "Default")
      (node (ref "C13") (pin "+") (pinfunction "+_+") (pintype "passive"))
      (node (ref "U$1") (pin "20") (pinfunction "VCAP_20") (pintype "bidirectional"))
    )
    (net (code "77") (name "Net-(U$1-~{RESET})") (class "Default")
      (node (ref "C8") (pin "1") (pinfunction "1_1") (pintype "passive"))
      (node (ref "R17") (pin "1") (pinfunction "1_1") (pintype "passive"))
      (node (ref "U$1") (pin "1") (pinfunction "~{RESET}_1") (pintype "bidirectional"))
    )
    (net (code "78") (name "Net-(U3-STBY)") (class "Default")
      (node (ref "R69") (pin "1") (pinfunction "1_1") (pintype "passive"))
      (node (ref "U3") (pin "8") (pinfunction "STBY_8") (pintype "input"))
    )
    (net (code "79") (name "PAIRED_STATE") (class "Default")
      (node (ref "IC1") (pin "6") (pinfunction "PD4(XCK/T0)_6") (pintype "bidirectional"))
      (node (ref "LED6") (pin "A") (pinfunction "A_A") (pintype "passive"))
      (node (ref "U1") (pin "32") (pinfunction "PIO9_32") (pintype "bidirectional"))
    )
    (net (code "80") (name "PWM_RX") (class "Default")
      (node (ref "IC9") (pin "1") (pinfunction "OUT_1") (pintype "open_collector"))
      (node (ref "R75") (pin "2") (pinfunction "2_2") (pintype "passive"))
      (node (ref "U$1") (pin "5") (pinfunction "PWM_RX_5") (pintype "bidirectional"))
    )
    (net (code "81") (name "PWM{slash}~{VPW}") (class "Default")
      (node (ref "Q5") (pin "1") (pinfunction "G_1") (pintype "passive"))
      (node (ref "U$1") (pin "3") (pinfunction "PWM/~{VPW}_3") (pintype "bidirectional"))
    )
    (net (code "82") (name "QS+") (class "Default")
      (node (ref "CON3") (pin "P$3") (pinfunction "P$3_P$3") (pintype "bidirectional"))
      (node (ref "IC1") (pin "4") (pinfunction "PD2(INT0)_4") (pintype "bidirectional"))
      (node (ref "R14") (pin "1") (pinfunction "1_1") (pintype "passive"))
    )
    (net (code "83") (name "RESET") (class "Default")
      (node (ref "C1") (pin "1") (pinfunction "1_1") (pintype "passive"))
      (node (ref "IC1") (pin "1") (pinfunction "PC6(/RESET)_1") (pintype "bidirectional"))
      (node (ref "R1") (pin "1") (pinfunction "1_1") (pintype "passive"))
      (node (ref "SV1") (pin "5") (pinfunction "5_5") (pintype "passive"))
    )
    (net (code "84") (name "RPM_INT") (class "Default")
      (node (ref "D2") (pin "C") (pinfunction "C_C") (pintype "passive"))
      (node (ref "IC1") (pin "5") (pinfunction "PD3(INT1)_5") (pintype "bidirectional"))
      (node (ref "R11") (pin "2") (pinfunction "2_2") (pintype "passive"))
      (node (ref "R13") (pin "1") (pinfunction "1_1") (pintype "passive"))
    )
    (net (code "85") (name "RXD") (class "Default")
      (node (ref "IC1") (pin "2") (pinfunction "PD0(RXD)_2") (pintype "bidirectional"))
      (node (ref "IC3") (pin "3") (pinfunction "O_3") (pintype "output"))
      (node (ref "IC3") (pin "8") (pinfunction "O_8") (pintype "output"))
    )
    (net (code "86") (name "RXD_BT") (class "Default")
      (node (ref "IC3") (pin "6") (pinfunction "O_6") (pintype "output"))
      (node (ref "U1") (pin "1") (pinfunction "TX_1") (pintype "bidirectional"))
    )
    (net (code "87") (name "RXD_OBD") (class "Default")
      (node (ref "IC3") (pin "11") (pinfunction "O_11") (pintype "output"))
      (node (ref "U$1") (pin "16") (pinfunction "UART_RX_16") (pintype "bidirectional"))
    )
    (net (code "88") (name "SCK") (class "Default")
      (node (ref "IC1") (pin "19") (pinfunction "PB5(SCK)_19") (pintype "bidirectional"))
      (node (ref "SV1") (pin "3") (pinfunction "3_3") (pintype "passive"))
    )
    (net (code "89") (name "TXD") (class "Default")
      (node (ref "IC1") (pin "3") (pinfunction "PD1(TXD)_3") (pintype "bidirectional"))
      (node (ref "IC3") (pin "12") (pinfunction "I0_12") (pintype "input"))
      (node (ref "IC3") (pin "4") (pinfunction "I0_4") (pintype "input"))
    )
    (net (code "90") (name "TXD_BT") (class "Default")
      (node (ref "IC3") (pin "1") (pinfunction "I0_1") (pintype "input"))
      (node (ref "U1") (pin "2") (pinfunction "RX_2") (pintype "bidirectional"))
    )
    (net (code "91") (name "TXD_OBD") (class "Default")
      (node (ref "IC3") (pin "9") (pinfunction "I0_9") (pintype "input"))
      (node (ref "R5") (pin "1") (pinfunction "1_1") (pintype "passive"))
      (node (ref "U$1") (pin "17") (pinfunction "UART_TX_17") (pintype "bidirectional"))
    )
    (net (code "92") (name "UART_EN_BT") (class "Default")
      (node (ref "IC1") (pin "11") (pinfunction "PD5(T1)_11") (pintype "bidirectional"))
      (node (ref "IC3") (pin "2") (pinfunction "I1_2") (pintype "input"))
      (node (ref "IC3") (pin "5") (pinfunction "I1_5") (pintype "input"))
      (node (ref "T3") (pin "2") (pinfunction "B_2") (pintype "passive"))
    )
    (net (code "93") (name "UART_EN_OBD") (class "Default")
      (node (ref "IC1") (pin "12") (pinfunction "PD6(AIN0)_12") (pintype "bidirectional"))
      (node (ref "IC3") (pin "10") (pinfunction "I1_10") (pintype "input"))
      (node (ref "IC3") (pin "13") (pinfunction "I1_13") (pintype "input"))
      (node (ref "T3") (pin "5") (pinfunction "B_5") (pintype "passive"))
    )
    (net (code "94") (name "V_J1850") (class "Default")
      (node (ref "IC10") (pin "4") (pinfunction "OUT_4") (pintype "passive"))
      (node (ref "Q7") (pin "2") (pinfunction "S_2") (pintype "passive"))
      (node (ref "R70") (pin "2") (pinfunction "2_2") (pintype "passive"))
      (node (ref "R77") (pin "2") (pinfunction "2_2") (pintype "passive"))
    )
    (net (code "95") (name "WORK_MODE") (class "Default")
      (node (ref "LED7") (pin "A") (pinfunction "A_A") (pintype "passive"))
      (node (ref "U1") (pin "31") (pinfunction "PIO8_31") (pintype "bidirectional"))
    )
    (net (code "96") (name "unconnected-(IC1-PB1(OC1A)-Pad15)") (class "Default")
      (node (ref "IC1") (pin "15") (pinfunction "PB1(OC1A)_15") (pintype "bidirectional"))
    )
    (net (code "97") (name "unconnected-(IC1-PB2(SS{slash}OC1B)-Pad16)") (class "Default")
      (node (ref "IC1") (pin "16") (pinfunction "PB2(SS/OC1B)_16") (pintype "bidirectional"))
    )
    (net (code "98") (name "unconnected-(IC1-PC3(ADC3)-Pad26)") (class "Default")
      (node (ref "IC1") (pin "26") (pinfunction "PC3(ADC3)_26") (pintype "bidirectional"))
    )
    (net (code "99") (name "unconnected-(IC1-PC4(ADC4{slash}SDA)-Pad27)") (class "Default")
      (node (ref "IC1") (pin "27") (pinfunction "PC4(ADC4/SDA)_27") (pintype "bidirectional"))
    )
    (net (code "100") (name "unconnected-(IC2-IS-Pad4)") (class "Default")
      (node (ref "IC2") (pin "4") (pinfunction "IS_4") (pintype "passive"))
    )
    (net (code "101") (name "unconnected-(S2-P1-Pad4)") (class "Default")
      (node (ref "S2") (pin "4") (pinfunction "P1_4") (pintype "passive"))
    )
    (net (code "102") (name "unconnected-(S2-S1-Pad2)") (class "Default")
      (node (ref "S2") (pin "2") (pinfunction "S1_2") (pintype "passive"))
    )
    (net (code "103") (name "unconnected-(SV1-Pad2)") (class "Default")
      (node (ref "SV1") (pin "2") (pinfunction "2_2") (pintype "passive"))
    )
    (net (code "104") (name "unconnected-(U$1-~{SLEEP}-Pad12)") (class "Default")
      (node (ref "U$1") (pin "12") (pinfunction "~{SLEEP}_12") (pintype "bidirectional"))
    )
    (net (code "105") (name "unconnected-(U1-AIO0-Pad9)") (class "Default")
      (node (ref "U1") (pin "9") (pinfunction "AIO0_9") (pintype "bidirectional"))
    )
    (net (code "106") (name "unconnected-(U1-AIO1-Pad10)") (class "Default")
      (node (ref "U1") (pin "10") (pinfunction "AIO1_10") (pintype "bidirectional"))
    )
    (net (code "107") (name "unconnected-(U1-CLK-Pad19)") (class "Default")
      (node (ref "U1") (pin "19") (pinfunction "CLK_19") (pintype "bidirectional"))
    )
    (net (code "108") (name "unconnected-(U1-CSB-Pad16)") (class "Default")
      (node (ref "U1") (pin "16") (pinfunction "CSB_16") (pintype "bidirectional"))
    )
    (net (code "109") (name "unconnected-(U1-CTS-Pad3)") (class "Default")
      (node (ref "U1") (pin "3") (pinfunction "CTS_3") (pintype "bidirectional"))
    )
    (net (code "110") (name "unconnected-(U1-MISO-Pad18)") (class "Default")
      (node (ref "U1") (pin "18") (pinfunction "MISO_18") (pintype "bidirectional"))
    )
    (net (code "111") (name "unconnected-(U1-MOSI-Pad17)") (class "Default")
      (node (ref "U1") (pin "17") (pinfunction "MOSI_17") (pintype "bidirectional"))
    )
    (net (code "112") (name "unconnected-(U1-NC-Pad14)") (class "Default")
      (node (ref "U1") (pin "14") (pinfunction "NC_14") (pintype "bidirectional"))
    )
    (net (code "113") (name "unconnected-(U1-PCM_CLK-Pad5)") (class "Default")
      (node (ref "U1") (pin "5") (pinfunction "PCM_CLK_5") (pintype "bidirectional"))
    )
    (net (code "114") (name "unconnected-(U1-PCM_IN-Pad7)") (class "Default")
      (node (ref "U1") (pin "7") (pinfunction "PCM_IN_7") (pintype "bidirectional"))
    )
    (net (code "115") (name "unconnected-(U1-PCM_OUT-Pad6)") (class "Default")
      (node (ref "U1") (pin "6") (pinfunction "PCM_OUT_6") (pintype "bidirectional"))
    )
    (net (code "116") (name "unconnected-(U1-PCN_SYNC-Pad8)") (class "Default")
      (node (ref "U1") (pin "8") (pinfunction "PCN_SYNC_8") (pintype "bidirectional"))
    )
    (net (code "117") (name "unconnected-(U1-PIO0-Pad23)") (class "Default")
      (node (ref "U1") (pin "23") (pinfunction "PIO0_23") (pintype "bidirectional"))
    )
    (net (code "118") (name "unconnected-(U1-PIO1-Pad24)") (class "Default")
      (node (ref "U1") (pin "24") (pinfunction "PIO1_24") (pintype "bidirectional"))
    )
    (net (code "119") (name "unconnected-(U1-PIO2-Pad25)") (class "Default")
      (node (ref "U1") (pin "25") (pinfunction "PIO2_25") (pintype "bidirectional"))
    )
    (net (code "120") (name "unconnected-(U1-PIO3-Pad26)") (class "Default")
      (node (ref "U1") (pin "26") (pinfunction "PIO3_26") (pintype "bidirectional"))
    )
    (net (code "121") (name "unconnected-(U1-PIO4-Pad27)") (class "Default")
      (node (ref "U1") (pin "27") (pinfunction "PIO4_27") (pintype "bidirectional"))
    )
    (net (code "122") (name "unconnected-(U1-PIO5-Pad28)") (class "Default")
      (node (ref "U1") (pin "28") (pinfunction "PIO5_28") (pintype "bidirectional"))
    )
    (net (code "123") (name "unconnected-(U1-PIO6-Pad29)") (class "Default")
      (node (ref "U1") (pin "29") (pinfunction "PIO6_29") (pintype "bidirectional"))
    )
    (net (code "124") (name "unconnected-(U1-PIO7-Pad30)") (class "Default")
      (node (ref "U1") (pin "30") (pinfunction "PIO7_30") (pintype "bidirectional"))
    )
    (net (code "125") (name "unconnected-(U1-PIO10-Pad33)") (class "Default")
      (node (ref "U1") (pin "33") (pinfunction "PIO10_33") (pintype "bidirectional"))
    )
    (net (code "126") (name "unconnected-(U1-RTS-Pad4)") (class "Default")
      (node (ref "U1") (pin "4") (pinfunction "RTS_4") (pintype "bidirectional"))
    )
    (net (code "127") (name "unconnected-(U1-VBUSD+-Pad20)") (class "Default")
      (node (ref "U1") (pin "20") (pinfunction "VBUSD+_20") (pintype "bidirectional"))
    )
    (net (code "128") (name "unconnected-(U1-VBUSD--Pad15)") (class "Default")
      (node (ref "U1") (pin "15") (pinfunction "VBUSD-_15") (pintype "bidirectional"))
    )
    (net (code "129") (name "~{ISO_K_TX}") (class "Default")
      (node (ref "R64") (pin "1") (pinfunction "1_1") (pintype "passive"))
      (node (ref "U$1") (pin "25") (pinfunction "~{ISO_K_TX}_25") (pintype "bidirectional"))
    )
    (net (code "130") (name "~{ISO_L_TX}") (class "Default")
      (node (ref "R66") (pin "1") (pinfunction "1_1") (pintype "passive"))
      (node (ref "U$1") (pin "26") (pinfunction "~{ISO_L_TX}_26") (pintype "bidirectional"))
    )
    (net (code "131") (name "~{ISO_RX}") (class "Default")
      (node (ref "IC9") (pin "2") (pinfunction "OUT_2") (pintype "open_collector"))
      (node (ref "R62") (pin "2") (pinfunction "2_2") (pintype "passive"))
      (node (ref "U$1") (pin "11") (pinfunction "~{ISO_RX}_11") (pintype "bidirectional"))
    )
    (net (code "132") (name "~{J1850_BUS-_TX}") (class "Default")
      (node (ref "R84") (pin "2") (pinfunction "2_2") (pintype "passive"))
      (node (ref "U$1") (pin "7") (pinfunction "~{J1850_BUS-_TX}_7") (pintype "bidirectional"))
    )
    (net (code "133") (name "~{OBD_RX_LED}") (class "Default")
      (node (ref "LED16") (pin "C") (pinfunction "C_C") (pintype "passive"))
      (node (ref "U$1") (pin "22") (pinfunction "~{OBD_RX_LED/}INT_22") (pintype "bidirectional"))
    )
    (net (code "134") (name "~{OBD_TX_LED}") (class "Default")
      (node (ref "LED17") (pin "C") (pinfunction "C_C") (pintype "passive"))
      (node (ref "R19") (pin "2") (pinfunction "2_2") (pintype "passive"))
      (node (ref "S2") (pin "1") (pinfunction "S_1") (pintype "passive"))
      (node (ref "U$1") (pin "21") (pinfunction "~{OBD_TX_LED/}RST_NVM_21") (pintype "bidirectional"))
    )
    (net (code "135") (name "~{UART_RX_LED}") (class "Default")
      (node (ref "LED14") (pin "C") (pinfunction "C_C") (pintype "passive"))
      (node (ref "U$1") (pin "24") (pinfunction "~{UART_RX_LED}_24") (pintype "bidirectional"))
    )
    (net (code "136") (name "~{UART_TX_LED}") (class "Default")
      (node (ref "LED15") (pin "C") (pinfunction "C_C") (pintype "passive"))
      (node (ref "U$1") (pin "23") (pinfunction "~{UART_TX_LED}_23") (pintype "bidirectional"))
    )
    (net (code "137") (name "~{VPW_RX}") (class "Default")
      (node (ref "IC9") (pin "14") (pinfunction "OUT_14") (pintype "open_collector"))
      (node (ref "R82") (pin "2") (pinfunction "2_2") (pintype "passive"))
      (node (ref "U$1") (pin "4") (pinfunction "~{VPW_RX}_4") (pintype "bidirectional"))
    )
  )
)
